# SM3320-BATT-EV.net
KiCad netlist of a schematic drawn in Altium Designer
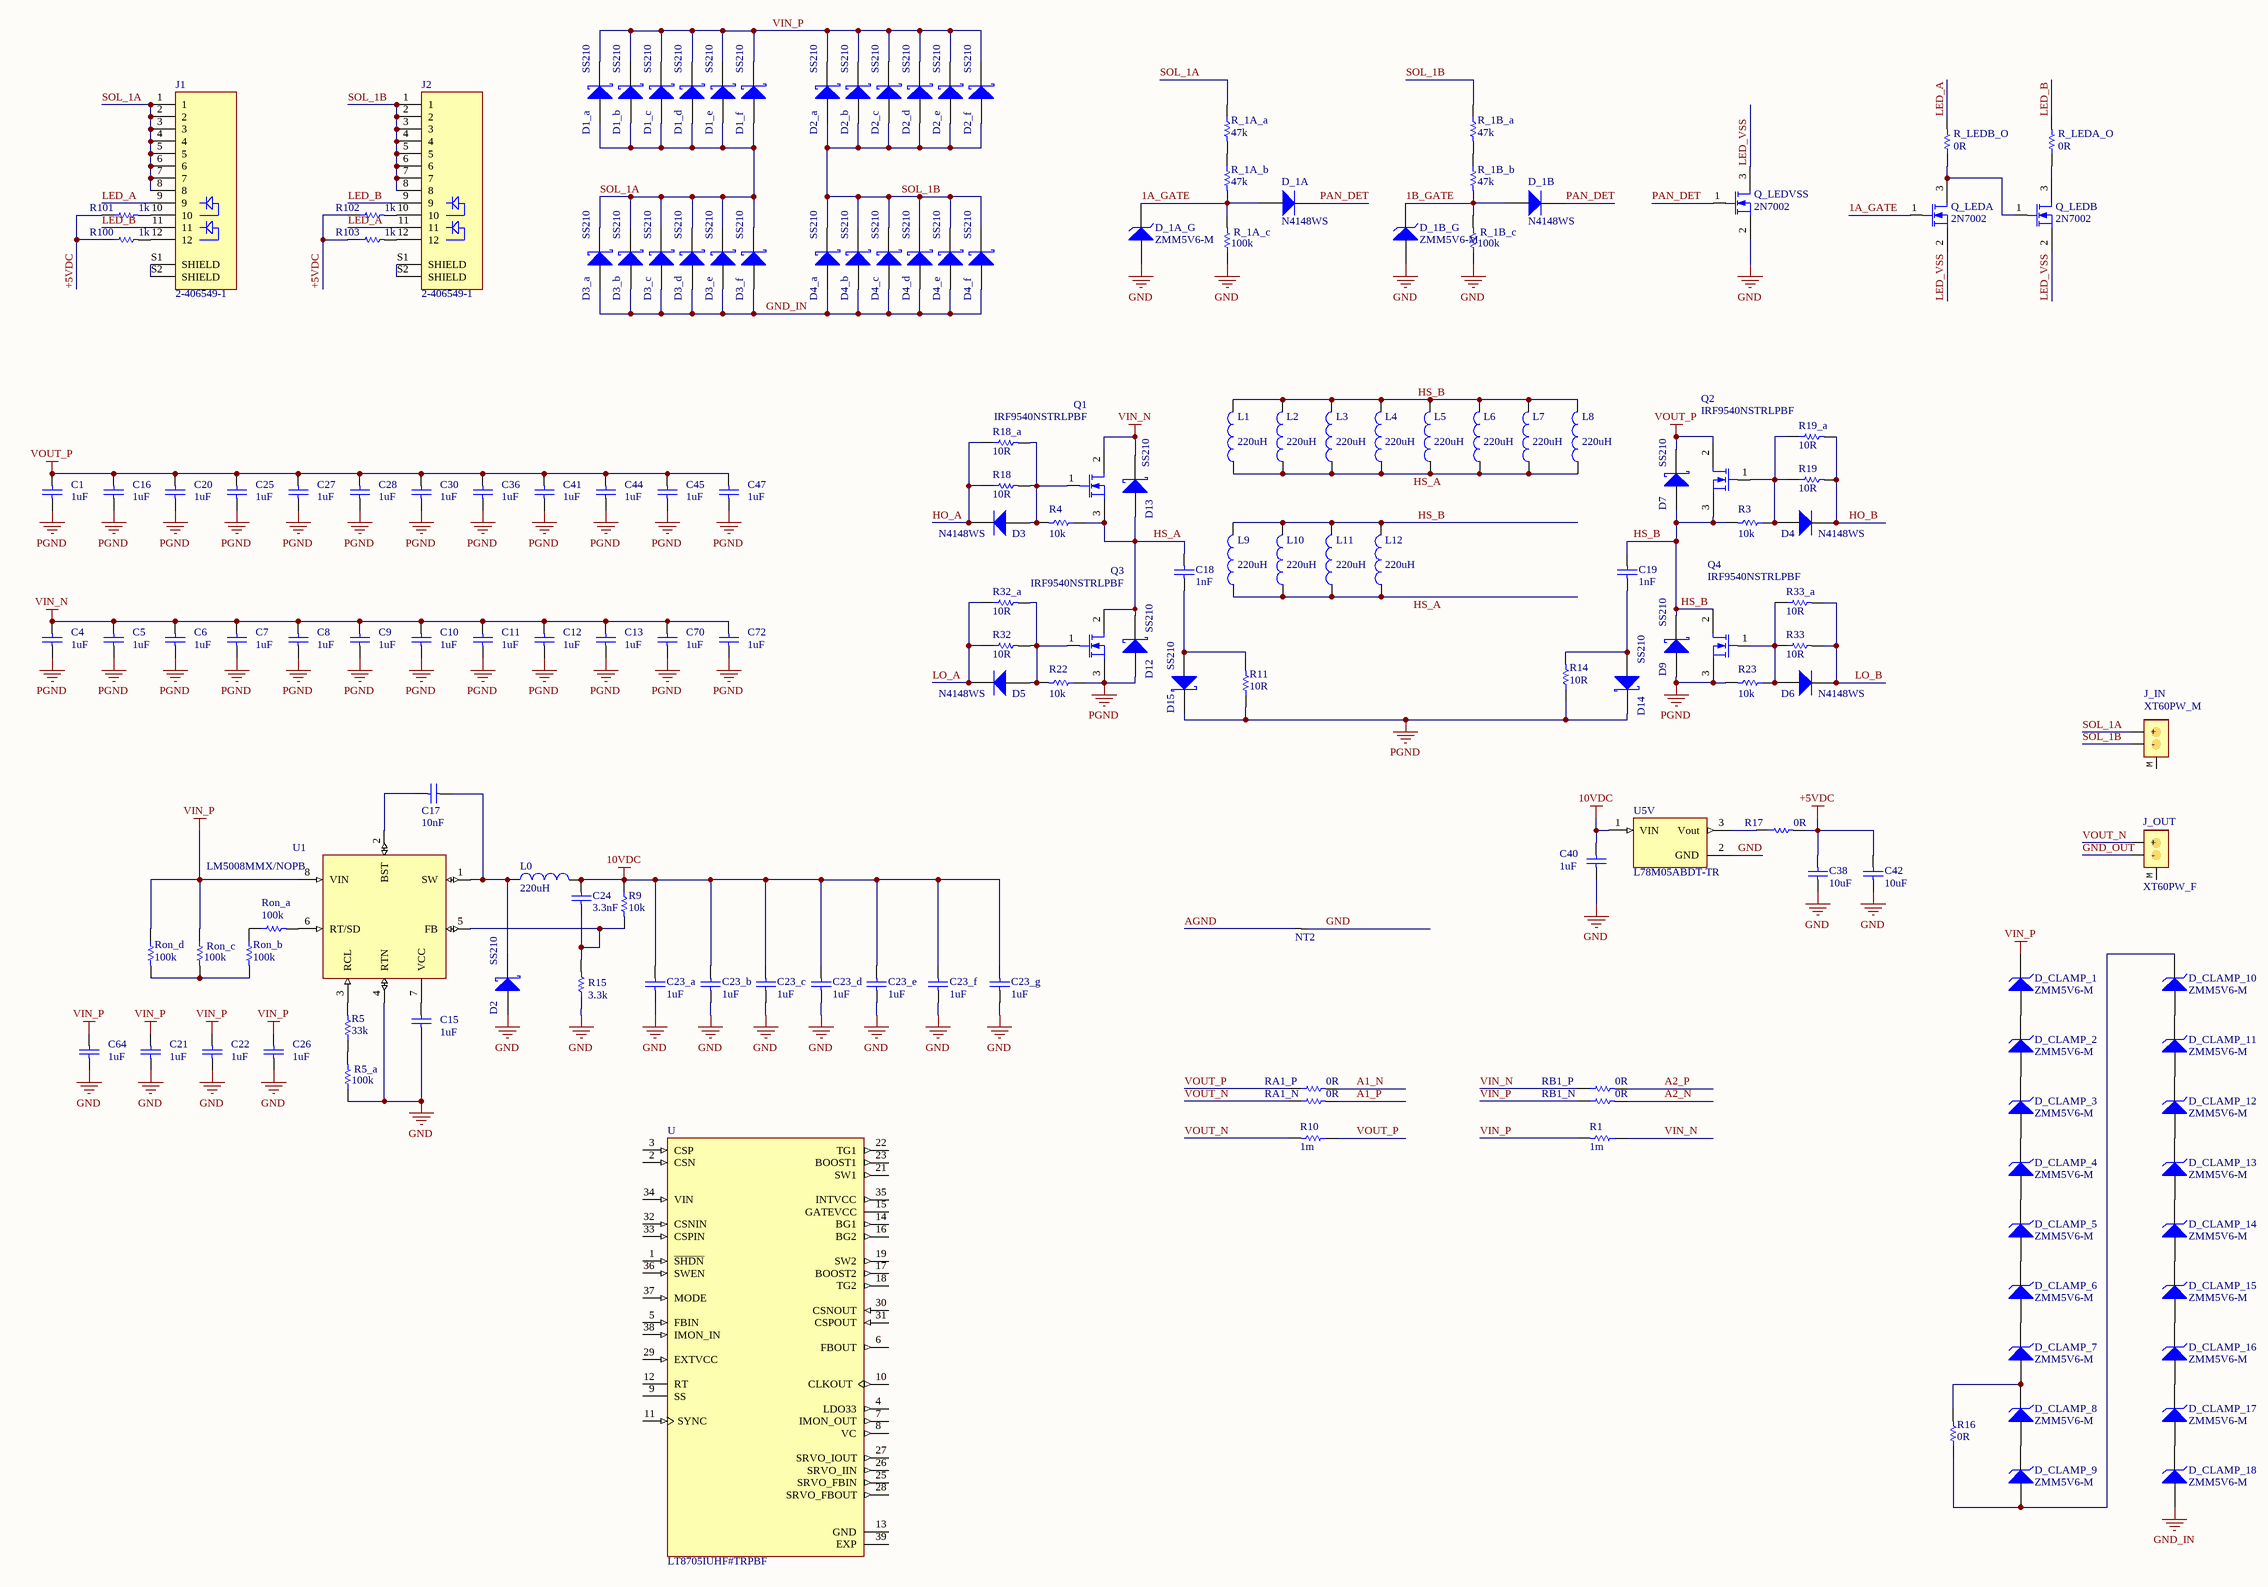
[diagram p0: SM3320-BATT-EV.SchDoc]

(export (version "E")
  (design (tool "Eeschema 10.0.6"))
  (components
    (comp (ref "C1")
      (value "1uF")
      (footprint "C_1206")
      (description "C - CAPACITOR - MLCC - 1uF - 100V - 1206 - X7R")
      (fields (field (name "LCSC PART #") "C91151") (field (name "Comment") "1206B105K101NT"))
      (libsource (lib "JLC_PCB") (part "1206B105K101NT"))
    )
    (comp (ref "C4")
      (value "1uF")
      (footprint "C_1206")
      (description "C - CAPACITOR - MLCC - 1uF - 100V - 1206 - X7R")
      (fields (field (name "LCSC PART #") "C91151") (field (name "Comment") "1206B105K101NT"))
      (libsource (lib "JLC_PCB") (part "1206B105K101NT"))
    )
    (comp (ref "C5")
      (value "1uF")
      (footprint "C_1206")
      (description "C - CAPACITOR - MLCC - 1uF - 100V - 1206 - X7R")
      (fields (field (name "LCSC PART #") "C91151") (field (name "Comment") "1206B105K101NT"))
      (libsource (lib "JLC_PCB") (part "1206B105K101NT"))
    )
    (comp (ref "C6")
      (value "1uF")
      (footprint "C_1206")
      (description "C - CAPACITOR - MLCC - 1uF - 100V - 1206 - X7R")
      (fields (field (name "LCSC PART #") "C91151") (field (name "Comment") "1206B105K101NT"))
      (libsource (lib "JLC_PCB") (part "1206B105K101NT"))
    )
    (comp (ref "C7")
      (value "1uF")
      (footprint "C_1206")
      (description "C - CAPACITOR - MLCC - 1uF - 100V - 1206 - X7R")
      (fields (field (name "LCSC PART #") "C91151") (field (name "Comment") "1206B105K101NT"))
      (libsource (lib "JLC_PCB") (part "1206B105K101NT"))
    )
    (comp (ref "C8")
      (value "1uF")
      (footprint "C_1206")
      (description "C - CAPACITOR - MLCC - 1uF - 100V - 1206 - X7R")
      (fields (field (name "LCSC PART #") "C91151") (field (name "Comment") "1206B105K101NT"))
      (libsource (lib "JLC_PCB") (part "1206B105K101NT"))
    )
    (comp (ref "C9")
      (value "1uF")
      (footprint "C_1206")
      (description "C - CAPACITOR - MLCC - 1uF - 100V - 1206 - X7R")
      (fields (field (name "LCSC PART #") "C91151") (field (name "Comment") "1206B105K101NT"))
      (libsource (lib "JLC_PCB") (part "1206B105K101NT"))
    )
    (comp (ref "C10")
      (value "1uF")
      (footprint "C_1206")
      (description "C - CAPACITOR - MLCC - 1uF - 100V - 1206 - X7R")
      (fields (field (name "LCSC PART #") "C91151") (field (name "Comment") "1206B105K101NT"))
      (libsource (lib "JLC_PCB") (part "1206B105K101NT"))
    )
    (comp (ref "C11")
      (value "1uF")
      (footprint "C_1206")
      (description "C - CAPACITOR - MLCC - 1uF - 100V - 1206 - X7R")
      (fields (field (name "LCSC PART #") "C91151") (field (name "Comment") "1206B105K101NT"))
      (libsource (lib "JLC_PCB") (part "1206B105K101NT"))
    )
    (comp (ref "C12")
      (value "1uF")
      (footprint "C_1206")
      (description "C - CAPACITOR - MLCC - 1uF - 100V - 1206 - X7R")
      (fields (field (name "LCSC PART #") "C91151") (field (name "Comment") "1206B105K101NT"))
      (libsource (lib "JLC_PCB") (part "1206B105K101NT"))
    )
    (comp (ref "C13")
      (value "1uF")
      (footprint "C_1206")
      (description "C - CAPACITOR - MLCC - 1uF - 100V - 1206 - X7R")
      (fields (field (name "LCSC PART #") "C91151") (field (name "Comment") "1206B105K101NT"))
      (libsource (lib "JLC_PCB") (part "1206B105K101NT"))
    )
    (comp (ref "C15")
      (value "1uF")
      (footprint "C_0402")
      (description "C - CAPACITOR - MLCC - 1uF - 25V - 0402")
      (fields (field (name "LCSC PART #") "C52923") (field (name "Comment") "CL05A105KA5NQNC"))
      (libsource (lib "JLC_PCB") (part "CL05A105KA5NQNC"))
    )
    (comp (ref "C16")
      (value "1uF")
      (footprint "C_1206")
      (description "C - CAPACITOR - MLCC - 1uF - 100V - 1206 - X7R")
      (fields (field (name "LCSC PART #") "C91151") (field (name "Comment") "1206B105K101NT"))
      (libsource (lib "JLC_PCB") (part "1206B105K101NT"))
    )
    (comp (ref "C17")
      (value "10nF")
      (footprint "C_0402")
      (description "C - CAPACITOR - MLCC - 10nF - 50V - 0402")
      (fields (field (name "LCSC PART #") "C15195") (field (name "Comment") "CL05B103KB5NNNC"))
      (libsource (lib "JLC_PCB") (part "CL05B103KB5NNNC"))
    )
    (comp (ref "C18")
      (value "1nF")
      (footprint "C_1206")
      (description "C - CAPACITOR - MLCC - 1nF - 2000V - 1206 - X7R")
      (fields (field (name "LCSC PART #") "C9196") (field (name "Comment") "1206B102K202NT"))
      (libsource (lib "JLC_PCB") (part "1206B102K202NT"))
    )
    (comp (ref "C19")
      (value "1nF")
      (footprint "C_1206")
      (description "C - CAPACITOR - MLCC - 1nF - 2000V - 1206 - X7R")
      (fields (field (name "LCSC PART #") "C9196") (field (name "Comment") "1206B102K202NT"))
      (libsource (lib "JLC_PCB") (part "1206B102K202NT"))
    )
    (comp (ref "C20")
      (value "1uF")
      (footprint "C_1206")
      (description "C - CAPACITOR - MLCC - 1uF - 100V - 1206 - X7R")
      (fields (field (name "LCSC PART #") "C91151") (field (name "Comment") "1206B105K101NT"))
      (libsource (lib "JLC_PCB") (part "1206B105K101NT"))
    )
    (comp (ref "C21")
      (value "1uF")
      (footprint "C_1206")
      (description "C - CAPACITOR - MLCC - 1uF - 100V - 1206 - X7R")
      (fields (field (name "LCSC PART #") "C91151") (field (name "Comment") "1206B105K101NT"))
      (libsource (lib "JLC_PCB") (part "1206B105K101NT"))
    )
    (comp (ref "C22")
      (value "1uF")
      (footprint "C_1206")
      (description "C - CAPACITOR - MLCC - 1uF - 100V - 1206 - X7R")
      (fields (field (name "LCSC PART #") "C91151") (field (name "Comment") "1206B105K101NT"))
      (libsource (lib "JLC_PCB") (part "1206B105K101NT"))
    )
    (comp (ref "C23_a")
      (value "1uF")
      (footprint "C_0402")
      (description "C - CAPACITOR - MLCC - 1uF - 25V - 0402")
      (fields (field (name "LCSC PART #") "C52923") (field (name "Comment") "CL05A105KA5NQNC"))
      (libsource (lib "JLC_PCB") (part "CL05A105KA5NQNC"))
    )
    (comp (ref "C23_b")
      (value "1uF")
      (footprint "C_0402")
      (description "C - CAPACITOR - MLCC - 1uF - 25V - 0402")
      (fields (field (name "LCSC PART #") "C52923") (field (name "Comment") "CL05A105KA5NQNC"))
      (libsource (lib "JLC_PCB") (part "CL05A105KA5NQNC"))
    )
    (comp (ref "C23_c")
      (value "1uF")
      (footprint "C_0402")
      (description "C - CAPACITOR - MLCC - 1uF - 25V - 0402")
      (fields (field (name "LCSC PART #") "C52923") (field (name "Comment") "CL05A105KA5NQNC"))
      (libsource (lib "JLC_PCB") (part "CL05A105KA5NQNC"))
    )
    (comp (ref "C23_d")
      (value "1uF")
      (footprint "C_0402")
      (description "C - CAPACITOR - MLCC - 1uF - 25V - 0402")
      (fields (field (name "LCSC PART #") "C52923") (field (name "Comment") "CL05A105KA5NQNC"))
      (libsource (lib "JLC_PCB") (part "CL05A105KA5NQNC"))
    )
    (comp (ref "C23_e")
      (value "1uF")
      (footprint "C_0402")
      (description "C - CAPACITOR - MLCC - 1uF - 25V - 0402")
      (fields (field (name "LCSC PART #") "C52923") (field (name "Comment") "CL05A105KA5NQNC"))
      (libsource (lib "JLC_PCB") (part "CL05A105KA5NQNC"))
    )
    (comp (ref "C23_f")
      (value "1uF")
      (footprint "C_0402")
      (description "C - CAPACITOR - MLCC - 1uF - 25V - 0402")
      (fields (field (name "LCSC PART #") "C52923") (field (name "Comment") "CL05A105KA5NQNC"))
      (libsource (lib "JLC_PCB") (part "CL05A105KA5NQNC"))
    )
    (comp (ref "C23_g")
      (value "1uF")
      (footprint "C_0402")
      (description "C - CAPACITOR - MLCC - 1uF - 25V - 0402")
      (fields (field (name "LCSC PART #") "C52923") (field (name "Comment") "CL05A105KA5NQNC"))
      (libsource (lib "JLC_PCB") (part "CL05A105KA5NQNC"))
    )
    (comp (ref "C24")
      (value "3.3nF")
      (footprint "C_0402")
      (description "C - CAPACITOR - MLCC - 3.3nF - 50V - 0402")
      (fields (field (name "LCSC PART #") "C26404") (field (name "Comment") "CL05B332KB5NNNC"))
      (libsource (lib "JLC_PCB") (part "CL05B332KB5NNNC"))
    )
    (comp (ref "C25")
      (value "1uF")
      (footprint "C_1206")
      (description "C - CAPACITOR - MLCC - 1uF - 100V - 1206 - X7R")
      (fields (field (name "LCSC PART #") "C91151") (field (name "Comment") "1206B105K101NT"))
      (libsource (lib "JLC_PCB") (part "1206B105K101NT"))
    )
    (comp (ref "C26")
      (value "1uF")
      (footprint "C_1206")
      (description "C - CAPACITOR - MLCC - 1uF - 100V - 1206 - X7R")
      (fields (field (name "LCSC PART #") "C91151") (field (name "Comment") "1206B105K101NT"))
      (libsource (lib "JLC_PCB") (part "1206B105K101NT"))
    )
    (comp (ref "C27")
      (value "1uF")
      (footprint "C_1206")
      (description "C - CAPACITOR - MLCC - 1uF - 100V - 1206 - X7R")
      (fields (field (name "LCSC PART #") "C91151") (field (name "Comment") "1206B105K101NT"))
      (libsource (lib "JLC_PCB") (part "1206B105K101NT"))
    )
    (comp (ref "C28")
      (value "1uF")
      (footprint "C_1206")
      (description "C - CAPACITOR - MLCC - 1uF - 100V - 1206 - X7R")
      (fields (field (name "LCSC PART #") "C91151") (field (name "Comment") "1206B105K101NT"))
      (libsource (lib "JLC_PCB") (part "1206B105K101NT"))
    )
    (comp (ref "C30")
      (value "1uF")
      (footprint "C_1206")
      (description "C - CAPACITOR - MLCC - 1uF - 100V - 1206 - X7R")
      (fields (field (name "LCSC PART #") "C91151") (field (name "Comment") "1206B105K101NT"))
      (libsource (lib "JLC_PCB") (part "1206B105K101NT"))
    )
    (comp (ref "C36")
      (value "1uF")
      (footprint "C_1206")
      (description "C - CAPACITOR - MLCC - 1uF - 100V - 1206 - X7R")
      (fields (field (name "LCSC PART #") "C91151") (field (name "Comment") "1206B105K101NT"))
      (libsource (lib "JLC_PCB") (part "1206B105K101NT"))
    )
    (comp (ref "C38")
      (value "10uF")
      (footprint "C_0402")
      (description "C - CAPACITOR - MLCC - 10uF - 6.3V - 0402")
      (fields (field (name "LCSC PART #") "C15525") (field (name "Comment") "CL05A106MQ5NUNC"))
      (libsource (lib "JLC_PCB") (part "CL05A106MQ5NUNC"))
    )
    (comp (ref "C40")
      (value "1uF")
      (footprint "C_0402")
      (description "C - CAPACITOR - MLCC - 1uF - 25V - 0402")
      (fields (field (name "LCSC PART #") "C52923") (field (name "Comment") "CL05A105KA5NQNC"))
      (libsource (lib "JLC_PCB") (part "CL05A105KA5NQNC"))
    )
    (comp (ref "C41")
      (value "1uF")
      (footprint "C_1206")
      (description "C - CAPACITOR - MLCC - 1uF - 100V - 1206 - X7R")
      (fields (field (name "LCSC PART #") "C91151") (field (name "Comment") "1206B105K101NT"))
      (libsource (lib "JLC_PCB") (part "1206B105K101NT"))
    )
    (comp (ref "C42")
      (value "10uF")
      (footprint "C_0402")
      (description "C - CAPACITOR - MLCC - 10uF - 6.3V - 0402")
      (fields (field (name "LCSC PART #") "C15525") (field (name "Comment") "CL05A106MQ5NUNC"))
      (libsource (lib "JLC_PCB") (part "CL05A106MQ5NUNC"))
    )
    (comp (ref "C44")
      (value "1uF")
      (footprint "C_1206")
      (description "C - CAPACITOR - MLCC - 1uF - 100V - 1206 - X7R")
      (fields (field (name "LCSC PART #") "C91151") (field (name "Comment") "1206B105K101NT"))
      (libsource (lib "JLC_PCB") (part "1206B105K101NT"))
    )
    (comp (ref "C45")
      (value "1uF")
      (footprint "C_1206")
      (description "C - CAPACITOR - MLCC - 1uF - 100V - 1206 - X7R")
      (fields (field (name "LCSC PART #") "C91151") (field (name "Comment") "1206B105K101NT"))
      (libsource (lib "JLC_PCB") (part "1206B105K101NT"))
    )
    (comp (ref "C47")
      (value "1uF")
      (footprint "C_1206")
      (description "C - CAPACITOR - MLCC - 1uF - 100V - 1206 - X7R")
      (fields (field (name "LCSC PART #") "C91151") (field (name "Comment") "1206B105K101NT"))
      (libsource (lib "JLC_PCB") (part "1206B105K101NT"))
    )
    (comp (ref "C64")
      (value "1uF")
      (footprint "C_1206")
      (description "C - CAPACITOR - MLCC - 1uF - 100V - 1206 - X7R")
      (fields (field (name "LCSC PART #") "C91151") (field (name "Comment") "1206B105K101NT"))
      (libsource (lib "JLC_PCB") (part "1206B105K101NT"))
    )
    (comp (ref "C70")
      (value "1uF")
      (footprint "C_1206")
      (description "C - CAPACITOR - MLCC - 1uF - 100V - 1206 - X7R")
      (fields (field (name "LCSC PART #") "C91151") (field (name "Comment") "1206B105K101NT"))
      (libsource (lib "JLC_PCB") (part "1206B105K101NT"))
    )
    (comp (ref "C72")
      (value "1uF")
      (footprint "C_1206")
      (description "C - CAPACITOR - MLCC - 1uF - 100V - 1206 - X7R")
      (fields (field (name "LCSC PART #") "C91151") (field (name "Comment") "1206B105K101NT"))
      (libsource (lib "JLC_PCB") (part "1206B105K101NT"))
    )
    (comp (ref "D1_a")
      (value "SS210")
      (footprint "DO-214AC")
      (description "D - DIODE - SCHOTTKY - 100V - 2A")
      (fields (field (name "LCSC PART #") "C14996"))
      (libsource (lib "JLC_PCB") (part "SS210"))
    )
    (comp (ref "D1_b")
      (value "SS210")
      (footprint "DO-214AC")
      (description "D - DIODE - SCHOTTKY - 100V - 2A")
      (fields (field (name "LCSC PART #") "C14996"))
      (libsource (lib "JLC_PCB") (part "SS210"))
    )
    (comp (ref "D1_c")
      (value "SS210")
      (footprint "DO-214AC")
      (description "D - DIODE - SCHOTTKY - 100V - 2A")
      (fields (field (name "LCSC PART #") "C14996"))
      (libsource (lib "JLC_PCB") (part "SS210"))
    )
    (comp (ref "D1_d")
      (value "SS210")
      (footprint "DO-214AC")
      (description "D - DIODE - SCHOTTKY - 100V - 2A")
      (fields (field (name "LCSC PART #") "C14996"))
      (libsource (lib "JLC_PCB") (part "SS210"))
    )
    (comp (ref "D1_e")
      (value "SS210")
      (footprint "DO-214AC")
      (description "D - DIODE - SCHOTTKY - 100V - 2A")
      (fields (field (name "LCSC PART #") "C14996"))
      (libsource (lib "JLC_PCB") (part "SS210"))
    )
    (comp (ref "D1_f")
      (value "SS210")
      (footprint "DO-214AC")
      (description "D - DIODE - SCHOTTKY - 100V - 2A")
      (fields (field (name "LCSC PART #") "C14996"))
      (libsource (lib "JLC_PCB") (part "SS210"))
    )
    (comp (ref "D2")
      (value "SS210")
      (footprint "DO-214AC")
      (description "D - DIODE - SCHOTTKY - 100V - 2A")
      (fields (field (name "LCSC PART #") "C14996"))
      (libsource (lib "JLC_PCB") (part "SS210"))
    )
    (comp (ref "D2_a")
      (value "SS210")
      (footprint "DO-214AC")
      (description "D - DIODE - SCHOTTKY - 100V - 2A")
      (fields (field (name "LCSC PART #") "C14996"))
      (libsource (lib "JLC_PCB") (part "SS210"))
    )
    (comp (ref "D2_b")
      (value "SS210")
      (footprint "DO-214AC")
      (description "D - DIODE - SCHOTTKY - 100V - 2A")
      (fields (field (name "LCSC PART #") "C14996"))
      (libsource (lib "JLC_PCB") (part "SS210"))
    )
    (comp (ref "D2_c")
      (value "SS210")
      (footprint "DO-214AC")
      (description "D - DIODE - SCHOTTKY - 100V - 2A")
      (fields (field (name "LCSC PART #") "C14996"))
      (libsource (lib "JLC_PCB") (part "SS210"))
    )
    (comp (ref "D2_d")
      (value "SS210")
      (footprint "DO-214AC")
      (description "D - DIODE - SCHOTTKY - 100V - 2A")
      (fields (field (name "LCSC PART #") "C14996"))
      (libsource (lib "JLC_PCB") (part "SS210"))
    )
    (comp (ref "D2_e")
      (value "SS210")
      (footprint "DO-214AC")
      (description "D - DIODE - SCHOTTKY - 100V - 2A")
      (fields (field (name "LCSC PART #") "C14996"))
      (libsource (lib "JLC_PCB") (part "SS210"))
    )
    (comp (ref "D2_f")
      (value "SS210")
      (footprint "DO-214AC")
      (description "D - DIODE - SCHOTTKY - 100V - 2A")
      (fields (field (name "LCSC PART #") "C14996"))
      (libsource (lib "JLC_PCB") (part "SS210"))
    )
    (comp (ref "D3")
      (value "N4148WS")
      (footprint "SOD-323")
      (description "D - DIODE - FAST TRR - 100V - 150mA - 4ns")
      (fields (field (name "LCSC PART #") "C2128"))
      (libsource (lib "JLC_PCB") (part "N4148WS"))
    )
    (comp (ref "D3_a")
      (value "SS210")
      (footprint "DO-214AC")
      (description "D - DIODE - SCHOTTKY - 100V - 2A")
      (fields (field (name "LCSC PART #") "C14996"))
      (libsource (lib "JLC_PCB") (part "SS210"))
    )
    (comp (ref "D3_b")
      (value "SS210")
      (footprint "DO-214AC")
      (description "D - DIODE - SCHOTTKY - 100V - 2A")
      (fields (field (name "LCSC PART #") "C14996"))
      (libsource (lib "JLC_PCB") (part "SS210"))
    )
    (comp (ref "D3_c")
      (value "SS210")
      (footprint "DO-214AC")
      (description "D - DIODE - SCHOTTKY - 100V - 2A")
      (fields (field (name "LCSC PART #") "C14996"))
      (libsource (lib "JLC_PCB") (part "SS210"))
    )
    (comp (ref "D3_d")
      (value "SS210")
      (footprint "DO-214AC")
      (description "D - DIODE - SCHOTTKY - 100V - 2A")
      (fields (field (name "LCSC PART #") "C14996"))
      (libsource (lib "JLC_PCB") (part "SS210"))
    )
    (comp (ref "D3_e")
      (value "SS210")
      (footprint "DO-214AC")
      (description "D - DIODE - SCHOTTKY - 100V - 2A")
      (fields (field (name "LCSC PART #") "C14996"))
      (libsource (lib "JLC_PCB") (part "SS210"))
    )
    (comp (ref "D3_f")
      (value "SS210")
      (footprint "DO-214AC")
      (description "D - DIODE - SCHOTTKY - 100V - 2A")
      (fields (field (name "LCSC PART #") "C14996"))
      (libsource (lib "JLC_PCB") (part "SS210"))
    )
    (comp (ref "D4")
      (value "N4148WS")
      (footprint "SOD-323")
      (description "D - DIODE - FAST TRR - 100V - 150mA - 4ns")
      (fields (field (name "LCSC PART #") "C2128"))
      (libsource (lib "JLC_PCB") (part "N4148WS"))
    )
    (comp (ref "D4_a")
      (value "SS210")
      (footprint "DO-214AC")
      (description "D - DIODE - SCHOTTKY - 100V - 2A")
      (fields (field (name "LCSC PART #") "C14996"))
      (libsource (lib "JLC_PCB") (part "SS210"))
    )
    (comp (ref "D4_b")
      (value "SS210")
      (footprint "DO-214AC")
      (description "D - DIODE - SCHOTTKY - 100V - 2A")
      (fields (field (name "LCSC PART #") "C14996"))
      (libsource (lib "JLC_PCB") (part "SS210"))
    )
    (comp (ref "D4_c")
      (value "SS210")
      (footprint "DO-214AC")
      (description "D - DIODE - SCHOTTKY - 100V - 2A")
      (fields (field (name "LCSC PART #") "C14996"))
      (libsource (lib "JLC_PCB") (part "SS210"))
    )
    (comp (ref "D4_d")
      (value "SS210")
      (footprint "DO-214AC")
      (description "D - DIODE - SCHOTTKY - 100V - 2A")
      (fields (field (name "LCSC PART #") "C14996"))
      (libsource (lib "JLC_PCB") (part "SS210"))
    )
    (comp (ref "D4_e")
      (value "SS210")
      (footprint "DO-214AC")
      (description "D - DIODE - SCHOTTKY - 100V - 2A")
      (fields (field (name "LCSC PART #") "C14996"))
      (libsource (lib "JLC_PCB") (part "SS210"))
    )
    (comp (ref "D4_f")
      (value "SS210")
      (footprint "DO-214AC")
      (description "D - DIODE - SCHOTTKY - 100V - 2A")
      (fields (field (name "LCSC PART #") "C14996"))
      (libsource (lib "JLC_PCB") (part "SS210"))
    )
    (comp (ref "D5")
      (value "N4148WS")
      (footprint "SOD-323")
      (description "D - DIODE - FAST TRR - 100V - 150mA - 4ns")
      (fields (field (name "LCSC PART #") "C2128"))
      (libsource (lib "JLC_PCB") (part "N4148WS"))
    )
    (comp (ref "D6")
      (value "N4148WS")
      (footprint "SOD-323")
      (description "D - DIODE - FAST TRR - 100V - 150mA - 4ns")
      (fields (field (name "LCSC PART #") "C2128"))
      (libsource (lib "JLC_PCB") (part "N4148WS"))
    )
    (comp (ref "D7")
      (value "SS210")
      (footprint "DO-214AC")
      (description "D - DIODE - SCHOTTKY - 100V - 2A")
      (fields (field (name "LCSC PART #") "C14996"))
      (libsource (lib "JLC_PCB") (part "SS210"))
    )
    (comp (ref "D9")
      (value "SS210")
      (footprint "DO-214AC")
      (description "D - DIODE - SCHOTTKY - 100V - 2A")
      (fields (field (name "LCSC PART #") "C14996"))
      (libsource (lib "JLC_PCB") (part "SS210"))
    )
    (comp (ref "D12")
      (value "SS210")
      (footprint "DO-214AC")
      (description "D - DIODE - SCHOTTKY - 100V - 2A")
      (fields (field (name "LCSC PART #") "C14996"))
      (libsource (lib "JLC_PCB") (part "SS210"))
    )
    (comp (ref "D13")
      (value "SS210")
      (footprint "DO-214AC")
      (description "D - DIODE - SCHOTTKY - 100V - 2A")
      (fields (field (name "LCSC PART #") "C14996"))
      (libsource (lib "JLC_PCB") (part "SS210"))
    )
    (comp (ref "D14")
      (value "SS210")
      (footprint "DO-214AC")
      (description "D - DIODE - SCHOTTKY - 100V - 2A")
      (fields (field (name "LCSC PART #") "C14996"))
      (libsource (lib "JLC_PCB") (part "SS210"))
    )
    (comp (ref "D15")
      (value "SS210")
      (footprint "DO-214AC")
      (description "D - DIODE - SCHOTTKY - 100V - 2A")
      (fields (field (name "LCSC PART #") "C14996"))
      (libsource (lib "JLC_PCB") (part "SS210"))
    )
    (comp (ref "D_1A")
      (value "N4148WS")
      (footprint "SOD-323")
      (description "D - DIODE - FAST TRR - 100V - 150mA - 4ns")
      (fields (field (name "LCSC PART #") "C2128"))
      (libsource (lib "JLC_PCB") (part "N4148WS"))
    )
    (comp (ref "D_1A_G")
      (value "ZMM5V6-M")
      (footprint "DO-213AA")
      (description "D - DIODE - ZENER - 5.6V - 500mW")
      (fields (field (name "LCSC PART #") "C8062"))
      (libsource (lib "JLC_PCB") (part "ZMM5V6-M"))
    )
    (comp (ref "D_1B")
      (value "N4148WS")
      (footprint "SOD-323")
      (description "D - DIODE - FAST TRR - 100V - 150mA - 4ns")
      (fields (field (name "LCSC PART #") "C2128"))
      (libsource (lib "JLC_PCB") (part "N4148WS"))
    )
    (comp (ref "D_1B_G")
      (value "ZMM5V6-M")
      (footprint "DO-213AA")
      (description "D - DIODE - ZENER - 5.6V - 500mW")
      (fields (field (name "LCSC PART #") "C8062"))
      (libsource (lib "JLC_PCB") (part "ZMM5V6-M"))
    )
    (comp (ref "D_CLAMP_1")
      (value "ZMM5V6-M")
      (footprint "DO-213AA")
      (description "D - DIODE - ZENER - 5.6V - 500mW")
      (fields (field (name "LCSC PART #") "C8062"))
      (libsource (lib "JLC_PCB") (part "ZMM5V6-M"))
    )
    (comp (ref "D_CLAMP_2")
      (value "ZMM5V6-M")
      (footprint "DO-213AA")
      (description "D - DIODE - ZENER - 5.6V - 500mW")
      (fields (field (name "LCSC PART #") "C8062"))
      (libsource (lib "JLC_PCB") (part "ZMM5V6-M"))
    )
    (comp (ref "D_CLAMP_3")
      (value "ZMM5V6-M")
      (footprint "DO-213AA")
      (description "D - DIODE - ZENER - 5.6V - 500mW")
      (fields (field (name "LCSC PART #") "C8062"))
      (libsource (lib "JLC_PCB") (part "ZMM5V6-M"))
    )
    (comp (ref "D_CLAMP_4")
      (value "ZMM5V6-M")
      (footprint "DO-213AA")
      (description "D - DIODE - ZENER - 5.6V - 500mW")
      (fields (field (name "LCSC PART #") "C8062"))
      (libsource (lib "JLC_PCB") (part "ZMM5V6-M"))
    )
    (comp (ref "D_CLAMP_5")
      (value "ZMM5V6-M")
      (footprint "DO-213AA")
      (description "D - DIODE - ZENER - 5.6V - 500mW")
      (fields (field (name "LCSC PART #") "C8062"))
      (libsource (lib "JLC_PCB") (part "ZMM5V6-M"))
    )
    (comp (ref "D_CLAMP_6")
      (value "ZMM5V6-M")
      (footprint "DO-213AA")
      (description "D - DIODE - ZENER - 5.6V - 500mW")
      (fields (field (name "LCSC PART #") "C8062"))
      (libsource (lib "JLC_PCB") (part "ZMM5V6-M"))
    )
    (comp (ref "D_CLAMP_7")
      (value "ZMM5V6-M")
      (footprint "DO-213AA")
      (description "D - DIODE - ZENER - 5.6V - 500mW")
      (fields (field (name "LCSC PART #") "C8062"))
      (libsource (lib "JLC_PCB") (part "ZMM5V6-M"))
    )
    (comp (ref "D_CLAMP_8")
      (value "ZMM5V6-M")
      (footprint "DO-213AA")
      (description "D - DIODE - ZENER - 5.6V - 500mW")
      (fields (field (name "LCSC PART #") "C8062"))
      (libsource (lib "JLC_PCB") (part "ZMM5V6-M"))
    )
    (comp (ref "D_CLAMP_9")
      (value "ZMM5V6-M")
      (footprint "DO-213AA")
      (description "D - DIODE - ZENER - 5.6V - 500mW")
      (fields (field (name "LCSC PART #") "C8062"))
      (libsource (lib "JLC_PCB") (part "ZMM5V6-M"))
    )
    (comp (ref "D_CLAMP_10")
      (value "ZMM5V6-M")
      (footprint "DO-213AA")
      (description "D - DIODE - ZENER - 5.6V - 500mW")
      (fields (field (name "LCSC PART #") "C8062"))
      (libsource (lib "JLC_PCB") (part "ZMM5V6-M"))
    )
    (comp (ref "D_CLAMP_11")
      (value "ZMM5V6-M")
      (footprint "DO-213AA")
      (description "D - DIODE - ZENER - 5.6V - 500mW")
      (fields (field (name "LCSC PART #") "C8062"))
      (libsource (lib "JLC_PCB") (part "ZMM5V6-M"))
    )
    (comp (ref "D_CLAMP_12")
      (value "ZMM5V6-M")
      (footprint "DO-213AA")
      (description "D - DIODE - ZENER - 5.6V - 500mW")
      (fields (field (name "LCSC PART #") "C8062"))
      (libsource (lib "JLC_PCB") (part "ZMM5V6-M"))
    )
    (comp (ref "D_CLAMP_13")
      (value "ZMM5V6-M")
      (footprint "DO-213AA")
      (description "D - DIODE - ZENER - 5.6V - 500mW")
      (fields (field (name "LCSC PART #") "C8062"))
      (libsource (lib "JLC_PCB") (part "ZMM5V6-M"))
    )
    (comp (ref "D_CLAMP_14")
      (value "ZMM5V6-M")
      (footprint "DO-213AA")
      (description "D - DIODE - ZENER - 5.6V - 500mW")
      (fields (field (name "LCSC PART #") "C8062"))
      (libsource (lib "JLC_PCB") (part "ZMM5V6-M"))
    )
    (comp (ref "D_CLAMP_15")
      (value "ZMM5V6-M")
      (footprint "DO-213AA")
      (description "D - DIODE - ZENER - 5.6V - 500mW")
      (fields (field (name "LCSC PART #") "C8062"))
      (libsource (lib "JLC_PCB") (part "ZMM5V6-M"))
    )
    (comp (ref "D_CLAMP_16")
      (value "ZMM5V6-M")
      (footprint "DO-213AA")
      (description "D - DIODE - ZENER - 5.6V - 500mW")
      (fields (field (name "LCSC PART #") "C8062"))
      (libsource (lib "JLC_PCB") (part "ZMM5V6-M"))
    )
    (comp (ref "D_CLAMP_17")
      (value "ZMM5V6-M")
      (footprint "DO-213AA")
      (description "D - DIODE - ZENER - 5.6V - 500mW")
      (fields (field (name "LCSC PART #") "C8062"))
      (libsource (lib "JLC_PCB") (part "ZMM5V6-M"))
    )
    (comp (ref "D_CLAMP_18")
      (value "ZMM5V6-M")
      (footprint "DO-213AA")
      (description "D - DIODE - ZENER - 5.6V - 500mW")
      (fields (field (name "LCSC PART #") "C8062"))
      (libsource (lib "JLC_PCB") (part "ZMM5V6-M"))
    )
    (comp (ref "J1")
      (value "2-406549-1")
      (footprint "TE_2-406549-1")
      (description "J - JACK - ETHERNET - Right - THT")
      (fields (field (name "LCSC PART #") "C125068"))
      (libsource (lib "JLC_PCB") (part "2-406549-1"))
    )
    (comp (ref "J2")
      (value "2-406549-1")
      (footprint "TE_2-406549-1")
      (description "J - JACK - ETHERNET - Right - THT")
      (fields (field (name "LCSC PART #") "C125068"))
      (libsource (lib "JLC_PCB") (part "2-406549-1"))
    )
    (comp (ref "J_IN")
      (value "XT60PW_M")
      (footprint "XT60PW_M")
      (description "J - JACK - POWER - XT60 - RIGHT - MALE")
      (fields (field (name "LCSC PART #") "X"))
      (libsource (lib "JLC_PCB") (part "XT60PW_M"))
    )
    (comp (ref "J_OUT")
      (value "XT60PW_F")
      (footprint "XT60PW_F")
      (description "J - JACK - POWER - XT60 - RIGHT - FEMALE")
      (fields (field (name "LCSC PART #") "X"))
      (libsource (lib "JLC_PCB") (part "XT60PW_F"))
    )
    (comp (ref "L0")
      (value "220uH")
      (footprint "SRR1260")
      (description "L - INDUCTOR - 220uH - 1.6A - 12.5mm")
      (fields (field (name "LCSC PART #") "C169380") (field (name "Comment") "SWRB1207S-221MT"))
      (libsource (lib "JLC_PCB") (part "SWRB1207S-221MT"))
    )
    (comp (ref "L1")
      (value "220uH")
      (footprint "SRR1260")
      (description "L - INDUCTOR - 220uH - 1.6A - 12.5mm")
      (fields (field (name "LCSC PART #") "C169380") (field (name "Comment") "SWRB1207S-221MT"))
      (libsource (lib "JLC_PCB") (part "SWRB1207S-221MT"))
    )
    (comp (ref "L2")
      (value "220uH")
      (footprint "SRR1260")
      (description "L - INDUCTOR - 220uH - 1.6A - 12.5mm")
      (fields (field (name "LCSC PART #") "C169380") (field (name "Comment") "SWRB1207S-221MT"))
      (libsource (lib "JLC_PCB") (part "SWRB1207S-221MT"))
    )
    (comp (ref "L3")
      (value "220uH")
      (footprint "SRR1260")
      (description "L - INDUCTOR - 220uH - 1.6A - 12.5mm")
      (fields (field (name "LCSC PART #") "C169380") (field (name "Comment") "SWRB1207S-221MT"))
      (libsource (lib "JLC_PCB") (part "SWRB1207S-221MT"))
    )
    (comp (ref "L4")
      (value "220uH")
      (footprint "SRR1260")
      (description "L - INDUCTOR - 220uH - 1.6A - 12.5mm")
      (fields (field (name "LCSC PART #") "C169380") (field (name "Comment") "SWRB1207S-221MT"))
      (libsource (lib "JLC_PCB") (part "SWRB1207S-221MT"))
    )
    (comp (ref "L5")
      (value "220uH")
      (footprint "SRR1260")
      (description "L - INDUCTOR - 220uH - 1.6A - 12.5mm")
      (fields (field (name "LCSC PART #") "C169380") (field (name "Comment") "SWRB1207S-221MT"))
      (libsource (lib "JLC_PCB") (part "SWRB1207S-221MT"))
    )
    (comp (ref "L6")
      (value "220uH")
      (footprint "SRR1260")
      (description "L - INDUCTOR - 220uH - 1.6A - 12.5mm")
      (fields (field (name "LCSC PART #") "C169380") (field (name "Comment") "SWRB1207S-221MT"))
      (libsource (lib "JLC_PCB") (part "SWRB1207S-221MT"))
    )
    (comp (ref "L7")
      (value "220uH")
      (footprint "SRR1260")
      (description "L - INDUCTOR - 220uH - 1.6A - 12.5mm")
      (fields (field (name "LCSC PART #") "C169380") (field (name "Comment") "SWRB1207S-221MT"))
      (libsource (lib "JLC_PCB") (part "SWRB1207S-221MT"))
    )
    (comp (ref "L8")
      (value "220uH")
      (footprint "SRR1260")
      (description "L - INDUCTOR - 220uH - 1.6A - 12.5mm")
      (fields (field (name "LCSC PART #") "C169380") (field (name "Comment") "SWRB1207S-221MT"))
      (libsource (lib "JLC_PCB") (part "SWRB1207S-221MT"))
    )
    (comp (ref "L9")
      (value "220uH")
      (footprint "SRR1260")
      (description "L - INDUCTOR - 220uH - 1.6A - 12.5mm")
      (fields (field (name "LCSC PART #") "C169380") (field (name "Comment") "SWRB1207S-221MT"))
      (libsource (lib "JLC_PCB") (part "SWRB1207S-221MT"))
    )
    (comp (ref "L10")
      (value "220uH")
      (footprint "SRR1260")
      (description "L - INDUCTOR - 220uH - 1.6A - 12.5mm")
      (fields (field (name "LCSC PART #") "C169380") (field (name "Comment") "SWRB1207S-221MT"))
      (libsource (lib "JLC_PCB") (part "SWRB1207S-221MT"))
    )
    (comp (ref "L11")
      (value "220uH")
      (footprint "SRR1260")
      (description "L - INDUCTOR - 220uH - 1.6A - 12.5mm")
      (fields (field (name "LCSC PART #") "C169380") (field (name "Comment") "SWRB1207S-221MT"))
      (libsource (lib "JLC_PCB") (part "SWRB1207S-221MT"))
    )
    (comp (ref "L12")
      (value "220uH")
      (footprint "SRR1260")
      (description "L - INDUCTOR - 220uH - 1.6A - 12.5mm")
      (fields (field (name "LCSC PART #") "C169380") (field (name "Comment") "SWRB1207S-221MT"))
      (libsource (lib "JLC_PCB") (part "SWRB1207S-221MT"))
    )
    (comp (ref "NT2")
      (value "0")
      (footprint "NET_TIE")
      (description "R - Net Tie")
      (libsource (lib "JLC_PCB") (part "NET_TIE"))
    )
    (comp (ref "Q1")
      (value "IRF9540NSTRLPBF")
      (footprint "TO-263-3")
      (description "Q - TRANSISTOR - MOSFET (N) - 250V - 33A - 0.094R")
      (fields (field (name "LCSC PART #") "C33903"))
      (libsource (lib "JLC_PCB") (part "IRF9540NSTRLPBF"))
    )
    (comp (ref "Q2")
      (value "IRF9540NSTRLPBF")
      (footprint "TO-263-3")
      (description "Q - TRANSISTOR - MOSFET (N) - 250V - 33A - 0.094R")
      (fields (field (name "LCSC PART #") "C33903"))
      (libsource (lib "JLC_PCB") (part "IRF9540NSTRLPBF"))
    )
    (comp (ref "Q3")
      (value "IRF9540NSTRLPBF")
      (footprint "TO-263-3")
      (description "Q - TRANSISTOR - MOSFET (N) - 250V - 33A - 0.094R")
      (fields (field (name "LCSC PART #") "C33903"))
      (libsource (lib "JLC_PCB") (part "IRF9540NSTRLPBF"))
    )
    (comp (ref "Q4")
      (value "IRF9540NSTRLPBF")
      (footprint "TO-263-3")
      (description "Q - TRANSISTOR - MOSFET (N) - 250V - 33A - 0.094R")
      (fields (field (name "LCSC PART #") "C33903"))
      (libsource (lib "JLC_PCB") (part "IRF9540NSTRLPBF"))
    )
    (comp (ref "Q_LEDA")
      (value "2N7002")
      (footprint "TO-236AB")
      (description "Q - TRANSISTOR - MOSFET (N) - 60V - 200mW")
      (fields (field (name "LCSC PART #") "C8545"))
      (libsource (lib "JLC_PCB") (part "2N7002"))
    )
    (comp (ref "Q_LEDB")
      (value "2N7002")
      (footprint "TO-236AB")
      (description "Q - TRANSISTOR - MOSFET (N) - 60V - 200mW")
      (fields (field (name "LCSC PART #") "C8545"))
      (libsource (lib "JLC_PCB") (part "2N7002"))
    )
    (comp (ref "Q_LEDVSS")
      (value "2N7002")
      (footprint "TO-236AB")
      (description "Q - TRANSISTOR - MOSFET (N) - 60V - 200mW")
      (fields (field (name "LCSC PART #") "C8545"))
      (libsource (lib "JLC_PCB") (part "2N7002"))
    )
    (comp (ref "R1")
      (value "1m")
      (footprint "R_2512")
      (description "R - RESISTOR - SMD - 0.001R - 1% - 2512 - 2W - 50ppm/k")
      (fields (field (name "LCSC PART #") "C349153") (field (name "POWER") "2W"))
      (libsource (lib "JLC_PCB") (part "EWSL2512F1L00S9"))
    )
    (comp (ref "R3")
      (value "10k")
      (footprint "R_0402")
      (description "R - RESISTOR - SMD - 10k - 1% - 0402")
      (fields (field (name "LCSC PART #") "C25744") (field (name "Comment") "0402WGF1002TCE"))
      (libsource (lib "JLC_PCB") (part "0402WGF1002TCE"))
    )
    (comp (ref "R4")
      (value "10k")
      (footprint "R_0402")
      (description "R - RESISTOR - SMD - 10k - 1% - 0402")
      (fields (field (name "LCSC PART #") "C25744") (field (name "Comment") "0402WGF1002TCE"))
      (libsource (lib "JLC_PCB") (part "0402WGF1002TCE"))
    )
    (comp (ref "R5")
      (value "33k")
      (footprint "R_0402")
      (description "R - RESISTOR - SMD - 33k - 1% - 0402")
      (fields (field (name "LCSC PART #") "C25779") (field (name "Comment") "0402WGF3302TCE"))
      (libsource (lib "JLC_PCB") (part "0402WGF3302TCE"))
    )
    (comp (ref "R5_a")
      (value "100k")
      (footprint "R_0402")
      (description "R - RESISTOR - SMD - 100k - 1% -  0402")
      (fields (field (name "LCSC PART #") "C25741") (field (name "Comment") "0402WGF1003TCE"))
      (libsource (lib "JLC_PCB") (part "0402WGF1003TCE"))
    )
    (comp (ref "R9")
      (value "10k")
      (footprint "R_0402")
      (description "R - RESISTOR - SMD - 10k - 1% - 0402")
      (fields (field (name "LCSC PART #") "C25744") (field (name "Comment") "0402WGF1002TCE"))
      (libsource (lib "JLC_PCB") (part "0402WGF1002TCE"))
    )
    (comp (ref "R10")
      (value "1m")
      (footprint "R_2512")
      (description "R - RESISTOR - SMD - 0.001R - 1% - 2512 - 2W - 50ppm/k")
      (fields (field (name "LCSC PART #") "C349153") (field (name "POWER") "2W"))
      (libsource (lib "JLC_PCB") (part "EWSL2512F1L00S9"))
    )
    (comp (ref "R11")
      (value "10R")
      (footprint "R_1206")
      (description "R - RESISTOR - SMD - 10R - 1% - 1206")
      (fields (field (name "LCSC PART #") "C17903") (field (name "Comment") "1206W4F100JT5E"))
      (libsource (lib "JLC_PCB") (part "1206W4F100JT5E"))
    )
    (comp (ref "R14")
      (value "10R")
      (footprint "R_1206")
      (description "R - RESISTOR - SMD - 10R - 1% - 1206")
      (fields (field (name "LCSC PART #") "C17903") (field (name "Comment") "1206W4F100JT5E"))
      (libsource (lib "JLC_PCB") (part "1206W4F100JT5E"))
    )
    (comp (ref "R15")
      (value "3.3k")
      (footprint "R_0402")
      (description "R - RESISTOR - SMD - 3.3k - 1% - 0402")
      (fields (field (name "LCSC PART #") "C25890") (field (name "Comment") "0402WGF3301TCE"))
      (libsource (lib "JLC_PCB") (part "0402WGF3301TCE"))
    )
    (comp (ref "R16")
      (value "0R")
      (footprint "R_0402")
      (description "R - RESISTOR - SMD - 0R - 1% - 0402")
      (fields (field (name "LCSC PART #") "C17168") (field (name "Comment") "0402WGF0000TCE"))
      (libsource (lib "JLC_PCB") (part "0402WGF0000TCE"))
    )
    (comp (ref "R17")
      (value "0R")
      (footprint "R_0402")
      (description "R - RESISTOR - SMD - 0R - 1% - 0402")
      (fields (field (name "LCSC PART #") "C17168") (field (name "Comment") "0402WGF0000TCE"))
      (libsource (lib "JLC_PCB") (part "0402WGF0000TCE"))
    )
    (comp (ref "R18")
      (value "10R")
      (footprint "R_0402")
      (description "R - RESISTOR - SMD - 10R - 1% - 0402")
      (fields (field (name "LCSC PART #") "C25077") (field (name "Comment") "0402WGF100JTCE"))
      (libsource (lib "JLC_PCB") (part "0402WGF100JTCE"))
    )
    (comp (ref "R18_a")
      (value "10R")
      (footprint "R_0402")
      (description "R - RESISTOR - SMD - 10R - 1% - 0402")
      (fields (field (name "LCSC PART #") "C25077") (field (name "Comment") "0402WGF100JTCE"))
      (libsource (lib "JLC_PCB") (part "0402WGF100JTCE"))
    )
    (comp (ref "R19")
      (value "10R")
      (footprint "R_0402")
      (description "R - RESISTOR - SMD - 10R - 1% - 0402")
      (fields (field (name "LCSC PART #") "C25077") (field (name "Comment") "0402WGF100JTCE"))
      (libsource (lib "JLC_PCB") (part "0402WGF100JTCE"))
    )
    (comp (ref "R19_a")
      (value "10R")
      (footprint "R_0402")
      (description "R - RESISTOR - SMD - 10R - 1% - 0402")
      (fields (field (name "LCSC PART #") "C25077") (field (name "Comment") "0402WGF100JTCE"))
      (libsource (lib "JLC_PCB") (part "0402WGF100JTCE"))
    )
    (comp (ref "R22")
      (value "10k")
      (footprint "R_0402")
      (description "R - RESISTOR - SMD - 10k - 1% - 0402")
      (fields (field (name "LCSC PART #") "C25744") (field (name "Comment") "0402WGF1002TCE"))
      (libsource (lib "JLC_PCB") (part "0402WGF1002TCE"))
    )
    (comp (ref "R23")
      (value "10k")
      (footprint "R_0402")
      (description "R - RESISTOR - SMD - 10k - 1% - 0402")
      (fields (field (name "LCSC PART #") "C25744") (field (name "Comment") "0402WGF1002TCE"))
      (libsource (lib "JLC_PCB") (part "0402WGF1002TCE"))
    )
    (comp (ref "R32")
      (value "10R")
      (footprint "R_0402")
      (description "R - RESISTOR - SMD - 10R - 1% - 0402")
      (fields (field (name "LCSC PART #") "C25077") (field (name "Comment") "0402WGF100JTCE"))
      (libsource (lib "JLC_PCB") (part "0402WGF100JTCE"))
    )
    (comp (ref "R32_a")
      (value "10R")
      (footprint "R_0402")
      (description "R - RESISTOR - SMD - 10R - 1% - 0402")
      (fields (field (name "LCSC PART #") "C25077") (field (name "Comment") "0402WGF100JTCE"))
      (libsource (lib "JLC_PCB") (part "0402WGF100JTCE"))
    )
    (comp (ref "R33")
      (value "10R")
      (footprint "R_0402")
      (description "R - RESISTOR - SMD - 10R - 1% - 0402")
      (fields (field (name "LCSC PART #") "C25077") (field (name "Comment") "0402WGF100JTCE"))
      (libsource (lib "JLC_PCB") (part "0402WGF100JTCE"))
    )
    (comp (ref "R33_a")
      (value "10R")
      (footprint "R_0402")
      (description "R - RESISTOR - SMD - 10R - 1% - 0402")
      (fields (field (name "LCSC PART #") "C25077") (field (name "Comment") "0402WGF100JTCE"))
      (libsource (lib "JLC_PCB") (part "0402WGF100JTCE"))
    )
    (comp (ref "R100")
      (value "1k")
      (footprint "R_0402")
      (description "R - RESISTOR - SMD - 1k - 1% - 0402")
      (fields (field (name "LCSC PART #") "C11702") (field (name "Comment") "0402WGF1001TCE"))
      (libsource (lib "JLC_PCB") (part "0402WGF1001TCE"))
    )
    (comp (ref "R101")
      (value "1k")
      (footprint "R_0402")
      (description "R - RESISTOR - SMD - 1k - 1% - 0402")
      (fields (field (name "LCSC PART #") "C11702") (field (name "Comment") "0402WGF1001TCE"))
      (libsource (lib "JLC_PCB") (part "0402WGF1001TCE"))
    )
    (comp (ref "R102")
      (value "1k")
      (footprint "R_0402")
      (description "R - RESISTOR - SMD - 1k - 1% - 0402")
      (fields (field (name "LCSC PART #") "C11702") (field (name "Comment") "0402WGF1001TCE"))
      (libsource (lib "JLC_PCB") (part "0402WGF1001TCE"))
    )
    (comp (ref "R103")
      (value "1k")
      (footprint "R_0402")
      (description "R - RESISTOR - SMD - 1k - 1% - 0402")
      (fields (field (name "LCSC PART #") "C11702") (field (name "Comment") "0402WGF1001TCE"))
      (libsource (lib "JLC_PCB") (part "0402WGF1001TCE"))
    )
    (comp (ref "RA1_N")
      (value "0R")
      (footprint "R_0402")
      (description "R - RESISTOR - SMD - 0R - 1% - 0402")
      (fields (field (name "LCSC PART #") "C17168") (field (name "Comment") "0402WGF0000TCE"))
      (libsource (lib "JLC_PCB") (part "0402WGF0000TCE"))
    )
    (comp (ref "RA1_P")
      (value "0R")
      (footprint "R_0402")
      (description "R - RESISTOR - SMD - 0R - 1% - 0402")
      (fields (field (name "LCSC PART #") "C17168") (field (name "Comment") "0402WGF0000TCE"))
      (libsource (lib "JLC_PCB") (part "0402WGF0000TCE"))
    )
    (comp (ref "RB1_N")
      (value "0R")
      (footprint "R_0402")
      (description "R - RESISTOR - SMD - 0R - 1% - 0402")
      (fields (field (name "LCSC PART #") "C17168") (field (name "Comment") "0402WGF0000TCE"))
      (libsource (lib "JLC_PCB") (part "0402WGF0000TCE"))
    )
    (comp (ref "RB1_P")
      (value "0R")
      (footprint "R_0402")
      (description "R - RESISTOR - SMD - 0R - 1% - 0402")
      (fields (field (name "LCSC PART #") "C17168") (field (name "Comment") "0402WGF0000TCE"))
      (libsource (lib "JLC_PCB") (part "0402WGF0000TCE"))
    )
    (comp (ref "Ron_a")
      (value "100k")
      (footprint "R_0402")
      (description "R - RESISTOR - SMD - 100k - 1% -  0402")
      (fields (field (name "LCSC PART #") "C25741") (field (name "Comment") "0402WGF1003TCE"))
      (libsource (lib "JLC_PCB") (part "0402WGF1003TCE"))
    )
    (comp (ref "Ron_b")
      (value "100k")
      (footprint "R_0402")
      (description "R - RESISTOR - SMD - 100k - 1% -  0402")
      (fields (field (name "LCSC PART #") "C25741") (field (name "Comment") "0402WGF1003TCE"))
      (libsource (lib "JLC_PCB") (part "0402WGF1003TCE"))
    )
    (comp (ref "Ron_c")
      (value "100k")
      (footprint "R_0402")
      (description "R - RESISTOR - SMD - 100k - 1% -  0402")
      (fields (field (name "LCSC PART #") "C25741") (field (name "Comment") "0402WGF1003TCE"))
      (libsource (lib "JLC_PCB") (part "0402WGF1003TCE"))
    )
    (comp (ref "Ron_d")
      (value "100k")
      (footprint "R_0402")
      (description "R - RESISTOR - SMD - 100k - 1% -  0402")
      (fields (field (name "LCSC PART #") "C25741") (field (name "Comment") "0402WGF1003TCE"))
      (libsource (lib "JLC_PCB") (part "0402WGF1003TCE"))
    )
    (comp (ref "R_1A_a")
      (value "47k")
      (footprint "R_0402")
      (description "R - RESISTOR - SMD - 47k - 1% - 0402")
      (fields (field (name "LCSC PART #") "C25792") (field (name "Comment") "0402WGF4702TCE"))
      (libsource (lib "JLC_PCB") (part "0402WGF4702TCE"))
    )
    (comp (ref "R_1A_b")
      (value "47k")
      (footprint "R_0402")
      (description "R - RESISTOR - SMD - 47k - 1% - 0402")
      (fields (field (name "LCSC PART #") "C25792") (field (name "Comment") "0402WGF4702TCE"))
      (libsource (lib "JLC_PCB") (part "0402WGF4702TCE"))
    )
    (comp (ref "R_1A_c")
      (value "100k")
      (footprint "R_0402")
      (description "R - RESISTOR - SMD - 100k - 1% -  0402")
      (fields (field (name "LCSC PART #") "C25741") (field (name "Comment") "0402WGF1003TCE"))
      (libsource (lib "JLC_PCB") (part "0402WGF1003TCE"))
    )
    (comp (ref "R_1B_a")
      (value "47k")
      (footprint "R_0402")
      (description "R - RESISTOR - SMD - 47k - 1% - 0402")
      (fields (field (name "LCSC PART #") "C25792") (field (name "Comment") "0402WGF4702TCE"))
      (libsource (lib "JLC_PCB") (part "0402WGF4702TCE"))
    )
    (comp (ref "R_1B_b")
      (value "47k")
      (footprint "R_0402")
      (description "R - RESISTOR - SMD - 47k - 1% - 0402")
      (fields (field (name "LCSC PART #") "C25792") (field (name "Comment") "0402WGF4702TCE"))
      (libsource (lib "JLC_PCB") (part "0402WGF4702TCE"))
    )
    (comp (ref "R_1B_c")
      (value "100k")
      (footprint "R_0402")
      (description "R - RESISTOR - SMD - 100k - 1% -  0402")
      (fields (field (name "LCSC PART #") "C25741") (field (name "Comment") "0402WGF1003TCE"))
      (libsource (lib "JLC_PCB") (part "0402WGF1003TCE"))
    )
    (comp (ref "R_LEDA_O")
      (value "0R")
      (footprint "R_0402")
      (description "R - RESISTOR - SMD - 0R - 1% - 0402")
      (fields (field (name "LCSC PART #") "C17168") (field (name "Comment") "0402WGF0000TCE"))
      (libsource (lib "JLC_PCB") (part "0402WGF0000TCE"))
    )
    (comp (ref "R_LEDB_O")
      (value "0R")
      (footprint "R_0402")
      (description "R - RESISTOR - SMD - 0R - 1% - 0402")
      (fields (field (name "LCSC PART #") "C17168") (field (name "Comment") "0402WGF0000TCE"))
      (libsource (lib "JLC_PCB") (part "0402WGF0000TCE"))
    )
    (comp (ref "U")
      (value "LT8705IUHF#TRPBF")
      (footprint "QFN-39-P0.5MM")
      (description "DC/DC Cntrlr Single-OUT Step Down/Step Up 400kHz Automotive 38-Pin QFN EP T/R")
      (fields (field (name "MP") "LT8705AIUHF#TRPBF") (field (name "LCSC PART #") "C674170"))
      (libsource (lib "JLC_PCB") (part "LT8705IUHF#TRPBF"))
    )
    (comp (ref "U1")
      (value "LM5008MMX/NOPB")
      (footprint "SOP65P490X110-8N")
      (description "U - IC - BUCK CONVERTER, ADJUSTABLE, 95V, 350mA")
      (libsource (lib "JLC_PCB") (part "LM5008MMX/NOPB"))
    )
    (comp (ref "U5V")
      (value "L78M05ABDT-TR")
      (footprint "TO-252AA")
      (description "U - IC - 5V Power Regulator")
      (fields (field (name "LCSC PART #") "C58069"))
      (libsource (lib "JLC_PCB") (part "L78M05ABDT-TR"))
    )
  )
  (nets
    (net (code "1") (name "+5VDC") (class "Default")
      (node (ref "C38") (pin "2") (pinfunction "2_2") (pintype "passive"))
      (node (ref "C42") (pin "2") (pinfunction "2_2") (pintype "passive"))
      (node (ref "R100") (pin "1") (pinfunction "1_1") (pintype "passive"))
      (node (ref "R101") (pin "1") (pinfunction "1_1") (pintype "passive"))
      (node (ref "R102") (pin "1") (pinfunction "1_1") (pintype "passive"))
      (node (ref "R103") (pin "1") (pinfunction "1_1") (pintype "passive"))
      (node (ref "R17") (pin "2") (pinfunction "2_2") (pintype "passive"))
    )
    (net (code "2") (name "/1A_GATE") (class "Default")
      (node (ref "D_1A") (pin "2") (pinfunction "A_2") (pintype "passive"))
      (node (ref "D_1A_G") (pin "1") (pinfunction "K_1") (pintype "passive"))
      (node (ref "Q_LEDA") (pin "1") (pinfunction "G_1") (pintype "passive"))
      (node (ref "R_1A_b") (pin "2") (pinfunction "2_2") (pintype "passive"))
      (node (ref "R_1A_c") (pin "2") (pinfunction "2_2") (pintype "passive"))
    )
    (net (code "3") (name "/1B_GATE") (class "Default")
      (node (ref "D_1B") (pin "2") (pinfunction "A_2") (pintype "passive"))
      (node (ref "D_1B_G") (pin "1") (pinfunction "K_1") (pintype "passive"))
      (node (ref "R_1B_b") (pin "2") (pinfunction "2_2") (pintype "passive"))
      (node (ref "R_1B_c") (pin "2") (pinfunction "2_2") (pintype "passive"))
    )
    (net (code "4") (name "/A1_N") (class "Default")
      (node (ref "RA1_P") (pin "2") (pinfunction "2_2") (pintype "passive"))
    )
    (net (code "5") (name "/A1_P") (class "Default")
      (node (ref "RA1_N") (pin "2") (pinfunction "2_2") (pintype "passive"))
    )
    (net (code "6") (name "/A2_N") (class "Default")
      (node (ref "RB1_N") (pin "2") (pinfunction "2_2") (pintype "passive"))
    )
    (net (code "7") (name "/A2_P") (class "Default")
      (node (ref "RB1_P") (pin "2") (pinfunction "2_2") (pintype "passive"))
    )
    (net (code "8") (name "/AGND") (class "Default")
      (node (ref "NT2") (pin "1") (pinfunction "1_1") (pintype "passive"))
    )
    (net (code "9") (name "/GND_OUT") (class "Default")
      (node (ref "J_OUT") (pin "MINUS") (pinfunction "-_MINUS") (pintype "passive"))
    )
    (net (code "10") (name "/HO_A") (class "Default")
      (node (ref "D3") (pin "1") (pinfunction "K_1") (pintype "passive"))
      (node (ref "R18") (pin "1") (pinfunction "1_1") (pintype "passive"))
      (node (ref "R18_a") (pin "1") (pinfunction "1_1") (pintype "passive"))
    )
    (net (code "11") (name "/HO_B") (class "Default")
      (node (ref "D4") (pin "1") (pinfunction "K_1") (pintype "passive"))
      (node (ref "R19") (pin "2") (pinfunction "2_2") (pintype "passive"))
      (node (ref "R19_a") (pin "2") (pinfunction "2_2") (pintype "passive"))
    )
    (net (code "12") (name "/HS_A") (class "Default")
      (node (ref "C18") (pin "2") (pinfunction "2_2") (pintype "passive"))
      (node (ref "D12") (pin "1") (pinfunction "K_1") (pintype "passive"))
      (node (ref "D13") (pin "2") (pinfunction "A_2") (pintype "passive"))
      (node (ref "L1") (pin "1") (pinfunction "1_1") (pintype "passive"))
      (node (ref "L10") (pin "1") (pinfunction "1_1") (pintype "passive"))
      (node (ref "L11") (pin "1") (pinfunction "1_1") (pintype "passive"))
      (node (ref "L12") (pin "1") (pinfunction "1_1") (pintype "passive"))
      (node (ref "L2") (pin "1") (pinfunction "1_1") (pintype "passive"))
      (node (ref "L3") (pin "1") (pinfunction "1_1") (pintype "passive"))
      (node (ref "L4") (pin "1") (pinfunction "1_1") (pintype "passive"))
      (node (ref "L5") (pin "1") (pinfunction "1_1") (pintype "passive"))
      (node (ref "L6") (pin "1") (pinfunction "1_1") (pintype "passive"))
      (node (ref "L7") (pin "1") (pinfunction "1_1") (pintype "passive"))
      (node (ref "L8") (pin "1") (pinfunction "1_1") (pintype "passive"))
      (node (ref "L9") (pin "1") (pinfunction "1_1") (pintype "passive"))
      (node (ref "Q1") (pin "3") (pinfunction "S_3") (pintype "passive"))
      (node (ref "Q3") (pin "2") (pinfunction "D_2") (pintype "passive"))
      (node (ref "R4") (pin "1") (pinfunction "1_1") (pintype "passive"))
    )
    (net (code "13") (name "/HS_B") (class "Default")
      (node (ref "C19") (pin "2") (pinfunction "2_2") (pintype "passive"))
      (node (ref "D7") (pin "2") (pinfunction "A_2") (pintype "passive"))
      (node (ref "D9") (pin "1") (pinfunction "K_1") (pintype "passive"))
      (node (ref "L1") (pin "2") (pinfunction "2_2") (pintype "passive"))
      (node (ref "L10") (pin "2") (pinfunction "2_2") (pintype "passive"))
      (node (ref "L11") (pin "2") (pinfunction "2_2") (pintype "passive"))
      (node (ref "L12") (pin "2") (pinfunction "2_2") (pintype "passive"))
      (node (ref "L2") (pin "2") (pinfunction "2_2") (pintype "passive"))
      (node (ref "L3") (pin "2") (pinfunction "2_2") (pintype "passive"))
      (node (ref "L4") (pin "2") (pinfunction "2_2") (pintype "passive"))
      (node (ref "L5") (pin "2") (pinfunction "2_2") (pintype "passive"))
      (node (ref "L6") (pin "2") (pinfunction "2_2") (pintype "passive"))
      (node (ref "L7") (pin "2") (pinfunction "2_2") (pintype "passive"))
      (node (ref "L8") (pin "2") (pinfunction "2_2") (pintype "passive"))
      (node (ref "L9") (pin "2") (pinfunction "2_2") (pintype "passive"))
      (node (ref "Q2") (pin "3") (pinfunction "S_3") (pintype "passive"))
      (node (ref "Q4") (pin "2") (pinfunction "D_2") (pintype "passive"))
      (node (ref "R3") (pin "2") (pinfunction "2_2") (pintype "passive"))
    )
    (net (code "14") (name "/LED_A") (class "Default")
      (node (ref "J1") (pin "9") (pinfunction "9_9") (pintype "passive"))
      (node (ref "J2") (pin "11") (pinfunction "11_11") (pintype "passive"))
      (node (ref "R_LEDB_O") (pin "2") (pinfunction "2_2") (pintype "passive"))
    )
    (net (code "15") (name "/LED_B") (class "Default")
      (node (ref "J1") (pin "11") (pinfunction "11_11") (pintype "passive"))
      (node (ref "J2") (pin "9") (pinfunction "9_9") (pintype "passive"))
      (node (ref "R_LEDA_O") (pin "2") (pinfunction "2_2") (pintype "passive"))
    )
    (net (code "16") (name "/LED_VSS") (class "Default")
      (node (ref "Q_LEDA") (pin "2") (pinfunction "S_2") (pintype "passive"))
      (node (ref "Q_LEDB") (pin "2") (pinfunction "S_2") (pintype "passive"))
      (node (ref "Q_LEDVSS") (pin "3") (pinfunction "D_3") (pintype "passive"))
    )
    (net (code "17") (name "/LO_A") (class "Default")
      (node (ref "D5") (pin "1") (pinfunction "K_1") (pintype "passive"))
      (node (ref "R32") (pin "1") (pinfunction "1_1") (pintype "passive"))
      (node (ref "R32_a") (pin "1") (pinfunction "1_1") (pintype "passive"))
    )
    (net (code "18") (name "/LO_B") (class "Default")
      (node (ref "D6") (pin "1") (pinfunction "K_1") (pintype "passive"))
      (node (ref "R33") (pin "2") (pinfunction "2_2") (pintype "passive"))
      (node (ref "R33_a") (pin "2") (pinfunction "2_2") (pintype "passive"))
    )
    (net (code "19") (name "/PAN_DET") (class "Default")
      (node (ref "D_1A") (pin "1") (pinfunction "K_1") (pintype "passive"))
      (node (ref "D_1B") (pin "1") (pinfunction "K_1") (pintype "passive"))
      (node (ref "Q_LEDVSS") (pin "1") (pinfunction "G_1") (pintype "passive"))
    )
    (net (code "20") (name "/SOL_1A") (class "Default")
      (node (ref "D1_a") (pin "2") (pinfunction "A_2") (pintype "passive"))
      (node (ref "D1_b") (pin "2") (pinfunction "A_2") (pintype "passive"))
      (node (ref "D1_c") (pin "2") (pinfunction "A_2") (pintype "passive"))
      (node (ref "D1_d") (pin "2") (pinfunction "A_2") (pintype "passive"))
      (node (ref "D1_e") (pin "2") (pinfunction "A_2") (pintype "passive"))
      (node (ref "D1_f") (pin "2") (pinfunction "A_2") (pintype "passive"))
      (node (ref "D3_a") (pin "1") (pinfunction "K_1") (pintype "passive"))
      (node (ref "D3_b") (pin "1") (pinfunction "K_1") (pintype "passive"))
      (node (ref "D3_c") (pin "1") (pinfunction "K_1") (pintype "passive"))
      (node (ref "D3_d") (pin "1") (pinfunction "K_1") (pintype "passive"))
      (node (ref "D3_e") (pin "1") (pinfunction "K_1") (pintype "passive"))
      (node (ref "D3_f") (pin "1") (pinfunction "K_1") (pintype "passive"))
      (node (ref "J1") (pin "1") (pinfunction "1_1") (pintype "passive"))
      (node (ref "J1") (pin "2") (pinfunction "2_2") (pintype "passive"))
      (node (ref "J1") (pin "3") (pinfunction "3_3") (pintype "passive"))
      (node (ref "J1") (pin "4") (pinfunction "4_4") (pintype "passive"))
      (node (ref "J1") (pin "5") (pinfunction "5_5") (pintype "passive"))
      (node (ref "J1") (pin "6") (pinfunction "6_6") (pintype "passive"))
      (node (ref "J1") (pin "7") (pinfunction "7_7") (pintype "passive"))
      (node (ref "J1") (pin "8") (pinfunction "8_8") (pintype "passive"))
      (node (ref "J_IN") (pin "PLUS") (pinfunction "+_PLUS") (pintype "passive"))
      (node (ref "R_1A_a") (pin "1") (pinfunction "1_1") (pintype "passive"))
    )
    (net (code "21") (name "/SOL_1B") (class "Default")
      (node (ref "D2_a") (pin "2") (pinfunction "A_2") (pintype "passive"))
      (node (ref "D2_b") (pin "2") (pinfunction "A_2") (pintype "passive"))
      (node (ref "D2_c") (pin "2") (pinfunction "A_2") (pintype "passive"))
      (node (ref "D2_d") (pin "2") (pinfunction "A_2") (pintype "passive"))
      (node (ref "D2_e") (pin "2") (pinfunction "A_2") (pintype "passive"))
      (node (ref "D2_f") (pin "2") (pinfunction "A_2") (pintype "passive"))
      (node (ref "D4_a") (pin "1") (pinfunction "K_1") (pintype "passive"))
      (node (ref "D4_b") (pin "1") (pinfunction "K_1") (pintype "passive"))
      (node (ref "D4_c") (pin "1") (pinfunction "K_1") (pintype "passive"))
      (node (ref "D4_d") (pin "1") (pinfunction "K_1") (pintype "passive"))
      (node (ref "D4_e") (pin "1") (pinfunction "K_1") (pintype "passive"))
      (node (ref "D4_f") (pin "1") (pinfunction "K_1") (pintype "passive"))
      (node (ref "J2") (pin "1") (pinfunction "1_1") (pintype "passive"))
      (node (ref "J2") (pin "2") (pinfunction "2_2") (pintype "passive"))
      (node (ref "J2") (pin "3") (pinfunction "3_3") (pintype "passive"))
      (node (ref "J2") (pin "4") (pinfunction "4_4") (pintype "passive"))
      (node (ref "J2") (pin "5") (pinfunction "5_5") (pintype "passive"))
      (node (ref "J2") (pin "6") (pinfunction "6_6") (pintype "passive"))
      (node (ref "J2") (pin "7") (pinfunction "7_7") (pintype "passive"))
      (node (ref "J2") (pin "8") (pinfunction "8_8") (pintype "passive"))
      (node (ref "J_IN") (pin "MINUS") (pinfunction "-_MINUS") (pintype "passive"))
      (node (ref "R_1B_a") (pin "1") (pinfunction "1_1") (pintype "passive"))
    )
    (net (code "22") (name "/VOUT_N") (class "Default")
      (node (ref "J_OUT") (pin "PLUS") (pinfunction "+_PLUS") (pintype "passive"))
      (node (ref "R10") (pin "2") (pinfunction "2_2") (pintype "passive"))
      (node (ref "RA1_N") (pin "1") (pinfunction "1_1") (pintype "passive"))
    )
    (net (code "23") (name "10VDC") (class "Default")
      (node (ref "C23_a") (pin "1") (pinfunction "1_1") (pintype "passive"))
      (node (ref "C23_b") (pin "1") (pinfunction "1_1") (pintype "passive"))
      (node (ref "C23_c") (pin "1") (pinfunction "1_1") (pintype "passive"))
      (node (ref "C23_d") (pin "1") (pinfunction "1_1") (pintype "passive"))
      (node (ref "C23_e") (pin "1") (pinfunction "1_1") (pintype "passive"))
      (node (ref "C23_f") (pin "1") (pinfunction "1_1") (pintype "passive"))
      (node (ref "C23_g") (pin "1") (pinfunction "1_1") (pintype "passive"))
      (node (ref "C24") (pin "2") (pinfunction "2_2") (pintype "passive"))
      (node (ref "C40") (pin "2") (pinfunction "2_2") (pintype "passive"))
      (node (ref "L0") (pin "2") (pinfunction "2_2") (pintype "passive"))
      (node (ref "R9") (pin "1") (pinfunction "1_1") (pintype "passive"))
      (node (ref "U5V") (pin "1") (pinfunction "VIN_1") (pintype "input"))
    )
    (net (code "24") (name "GND") (class "Default")
      (node (ref "C15") (pin "2") (pinfunction "2_2") (pintype "passive"))
      (node (ref "C21") (pin "1") (pinfunction "1_1") (pintype "passive"))
      (node (ref "C22") (pin "1") (pinfunction "1_1") (pintype "passive"))
      (node (ref "C23_a") (pin "2") (pinfunction "2_2") (pintype "passive"))
      (node (ref "C23_b") (pin "2") (pinfunction "2_2") (pintype "passive"))
      (node (ref "C23_c") (pin "2") (pinfunction "2_2") (pintype "passive"))
      (node (ref "C23_d") (pin "2") (pinfunction "2_2") (pintype "passive"))
      (node (ref "C23_e") (pin "2") (pinfunction "2_2") (pintype "passive"))
      (node (ref "C23_f") (pin "2") (pinfunction "2_2") (pintype "passive"))
      (node (ref "C23_g") (pin "2") (pinfunction "2_2") (pintype "passive"))
      (node (ref "C26") (pin "1") (pinfunction "1_1") (pintype "passive"))
      (node (ref "C38") (pin "1") (pinfunction "1_1") (pintype "passive"))
      (node (ref "C40") (pin "1") (pinfunction "1_1") (pintype "passive"))
      (node (ref "C42") (pin "1") (pinfunction "1_1") (pintype "passive"))
      (node (ref "C64") (pin "1") (pinfunction "1_1") (pintype "passive"))
      (node (ref "D2") (pin "2") (pinfunction "A_2") (pintype "passive"))
      (node (ref "D_1A_G") (pin "2") (pinfunction "A_2") (pintype "passive"))
      (node (ref "D_1B_G") (pin "2") (pinfunction "A_2") (pintype "passive"))
      (node (ref "NT2") (pin "2") (pinfunction "2_2") (pintype "passive"))
      (node (ref "Q_LEDVSS") (pin "2") (pinfunction "S_2") (pintype "passive"))
      (node (ref "R15") (pin "1") (pinfunction "1_1") (pintype "passive"))
      (node (ref "R5_a") (pin "1") (pinfunction "1_1") (pintype "passive"))
      (node (ref "R_1A_c") (pin "1") (pinfunction "1_1") (pintype "passive"))
      (node (ref "R_1B_c") (pin "1") (pinfunction "1_1") (pintype "passive"))
      (node (ref "U1") (pin "4") (pinfunction "RTN_4") (pintype "bidirectional"))
      (node (ref "U5V") (pin "2") (pinfunction "GND_2") (pintype "power_in"))
    )
    (net (code "25") (name "GND_IN") (class "Default")
      (node (ref "D3_a") (pin "2") (pinfunction "A_2") (pintype "passive"))
      (node (ref "D3_b") (pin "2") (pinfunction "A_2") (pintype "passive"))
      (node (ref "D3_c") (pin "2") (pinfunction "A_2") (pintype "passive"))
      (node (ref "D3_d") (pin "2") (pinfunction "A_2") (pintype "passive"))
      (node (ref "D3_e") (pin "2") (pinfunction "A_2") (pintype "passive"))
      (node (ref "D3_f") (pin "2") (pinfunction "A_2") (pintype "passive"))
      (node (ref "D4_a") (pin "2") (pinfunction "A_2") (pintype "passive"))
      (node (ref "D4_b") (pin "2") (pinfunction "A_2") (pintype "passive"))
      (node (ref "D4_c") (pin "2") (pinfunction "A_2") (pintype "passive"))
      (node (ref "D4_d") (pin "2") (pinfunction "A_2") (pintype "passive"))
      (node (ref "D4_e") (pin "2") (pinfunction "A_2") (pintype "passive"))
      (node (ref "D4_f") (pin "2") (pinfunction "A_2") (pintype "passive"))
      (node (ref "D_CLAMP_18") (pin "2") (pinfunction "A_2") (pintype "passive"))
    )
    (net (code "26") (name "Net-(D2-K)") (class "Default")
      (node (ref "C17") (pin "2") (pinfunction "2_2") (pintype "passive"))
      (node (ref "D2") (pin "1") (pinfunction "K_1") (pintype "passive"))
      (node (ref "L0") (pin "1") (pinfunction "1_1") (pintype "passive"))
      (node (ref "U1") (pin "1") (pinfunction "SW_1") (pintype "bidirectional"))
    )
    (net (code "27") (name "Net-(D3-A)") (class "Default")
      (node (ref "D3") (pin "2") (pinfunction "A_2") (pintype "passive"))
      (node (ref "Q1") (pin "1") (pinfunction "G_1") (pintype "passive"))
      (node (ref "R18") (pin "2") (pinfunction "2_2") (pintype "passive"))
      (node (ref "R18_a") (pin "2") (pinfunction "2_2") (pintype "passive"))
      (node (ref "R4") (pin "2") (pinfunction "2_2") (pintype "passive"))
    )
    (net (code "28") (name "Net-(D4-A)") (class "Default")
      (node (ref "D4") (pin "2") (pinfunction "A_2") (pintype "passive"))
      (node (ref "Q2") (pin "1") (pinfunction "G_1") (pintype "passive"))
      (node (ref "R19") (pin "1") (pinfunction "1_1") (pintype "passive"))
      (node (ref "R19_a") (pin "1") (pinfunction "1_1") (pintype "passive"))
      (node (ref "R3") (pin "1") (pinfunction "1_1") (pintype "passive"))
    )
    (net (code "29") (name "Net-(D5-A)") (class "Default")
      (node (ref "D5") (pin "2") (pinfunction "A_2") (pintype "passive"))
      (node (ref "Q3") (pin "1") (pinfunction "G_1") (pintype "passive"))
      (node (ref "R22") (pin "2") (pinfunction "2_2") (pintype "passive"))
      (node (ref "R32") (pin "2") (pinfunction "2_2") (pintype "passive"))
      (node (ref "R32_a") (pin "2") (pinfunction "2_2") (pintype "passive"))
    )
    (net (code "30") (name "Net-(D6-A)") (class "Default")
      (node (ref "D6") (pin "2") (pinfunction "A_2") (pintype "passive"))
      (node (ref "Q4") (pin "1") (pinfunction "G_1") (pintype "passive"))
      (node (ref "R23") (pin "1") (pinfunction "1_1") (pintype "passive"))
      (node (ref "R33") (pin "1") (pinfunction "1_1") (pintype "passive"))
      (node (ref "R33_a") (pin "1") (pinfunction "1_1") (pintype "passive"))
    )
    (net (code "31") (name "Net-(D14-A)") (class "Default")
      (node (ref "C19") (pin "1") (pinfunction "1_1") (pintype "passive"))
      (node (ref "D14") (pin "2") (pinfunction "A_2") (pintype "passive"))
      (node (ref "R14") (pin "2") (pinfunction "2_2") (pintype "passive"))
    )
    (net (code "32") (name "Net-(D15-A)") (class "Default")
      (node (ref "C18") (pin "1") (pinfunction "1_1") (pintype "passive"))
      (node (ref "D15") (pin "2") (pinfunction "A_2") (pintype "passive"))
      (node (ref "R11") (pin "2") (pinfunction "2_2") (pintype "passive"))
    )
    (net (code "33") (name "Net-(D_CLAMP_1-A)") (class "Default")
      (node (ref "D_CLAMP_1") (pin "2") (pinfunction "A_2") (pintype "passive"))
      (node (ref "D_CLAMP_2") (pin "1") (pinfunction "K_1") (pintype "passive"))
    )
    (net (code "34") (name "Net-(D_CLAMP_2-A)") (class "Default")
      (node (ref "D_CLAMP_2") (pin "2") (pinfunction "A_2") (pintype "passive"))
      (node (ref "D_CLAMP_3") (pin "1") (pinfunction "K_1") (pintype "passive"))
    )
    (net (code "35") (name "Net-(D_CLAMP_3-A)") (class "Default")
      (node (ref "D_CLAMP_3") (pin "2") (pinfunction "A_2") (pintype "passive"))
      (node (ref "D_CLAMP_4") (pin "1") (pinfunction "K_1") (pintype "passive"))
    )
    (net (code "36") (name "Net-(D_CLAMP_4-A)") (class "Default")
      (node (ref "D_CLAMP_4") (pin "2") (pinfunction "A_2") (pintype "passive"))
      (node (ref "D_CLAMP_5") (pin "1") (pinfunction "K_1") (pintype "passive"))
    )
    (net (code "37") (name "Net-(D_CLAMP_5-A)") (class "Default")
      (node (ref "D_CLAMP_5") (pin "2") (pinfunction "A_2") (pintype "passive"))
      (node (ref "D_CLAMP_6") (pin "1") (pinfunction "K_1") (pintype "passive"))
    )
    (net (code "38") (name "Net-(D_CLAMP_6-A)") (class "Default")
      (node (ref "D_CLAMP_6") (pin "2") (pinfunction "A_2") (pintype "passive"))
      (node (ref "D_CLAMP_7") (pin "1") (pinfunction "K_1") (pintype "passive"))
    )
    (net (code "39") (name "Net-(D_CLAMP_7-A)") (class "Default")
      (node (ref "D_CLAMP_7") (pin "2") (pinfunction "A_2") (pintype "passive"))
      (node (ref "D_CLAMP_8") (pin "1") (pinfunction "K_1") (pintype "passive"))
      (node (ref "R16") (pin "2") (pinfunction "2_2") (pintype "passive"))
    )
    (net (code "40") (name "Net-(D_CLAMP_8-A)") (class "Default")
      (node (ref "D_CLAMP_8") (pin "2") (pinfunction "A_2") (pintype "passive"))
      (node (ref "D_CLAMP_9") (pin "1") (pinfunction "K_1") (pintype "passive"))
    )
    (net (code "41") (name "Net-(D_CLAMP_10-A)") (class "Default")
      (node (ref "D_CLAMP_10") (pin "2") (pinfunction "A_2") (pintype "passive"))
      (node (ref "D_CLAMP_11") (pin "1") (pinfunction "K_1") (pintype "passive"))
    )
    (net (code "42") (name "Net-(D_CLAMP_10-K)") (class "Default")
      (node (ref "D_CLAMP_10") (pin "1") (pinfunction "K_1") (pintype "passive"))
      (node (ref "D_CLAMP_9") (pin "2") (pinfunction "A_2") (pintype "passive"))
      (node (ref "R16") (pin "1") (pinfunction "1_1") (pintype "passive"))
    )
    (net (code "43") (name "Net-(D_CLAMP_11-A)") (class "Default")
      (node (ref "D_CLAMP_11") (pin "2") (pinfunction "A_2") (pintype "passive"))
      (node (ref "D_CLAMP_12") (pin "1") (pinfunction "K_1") (pintype "passive"))
    )
    (net (code "44") (name "Net-(D_CLAMP_12-A)") (class "Default")
      (node (ref "D_CLAMP_12") (pin "2") (pinfunction "A_2") (pintype "passive"))
      (node (ref "D_CLAMP_13") (pin "1") (pinfunction "K_1") (pintype "passive"))
    )
    (net (code "45") (name "Net-(D_CLAMP_13-A)") (class "Default")
      (node (ref "D_CLAMP_13") (pin "2") (pinfunction "A_2") (pintype "passive"))
      (node (ref "D_CLAMP_14") (pin "1") (pinfunction "K_1") (pintype "passive"))
    )
    (net (code "46") (name "Net-(D_CLAMP_14-A)") (class "Default")
      (node (ref "D_CLAMP_14") (pin "2") (pinfunction "A_2") (pintype "passive"))
      (node (ref "D_CLAMP_15") (pin "1") (pinfunction "K_1") (pintype "passive"))
    )
    (net (code "47") (name "Net-(D_CLAMP_15-A)") (class "Default")
      (node (ref "D_CLAMP_15") (pin "2") (pinfunction "A_2") (pintype "passive"))
      (node (ref "D_CLAMP_16") (pin "1") (pinfunction "K_1") (pintype "passive"))
    )
    (net (code "48") (name "Net-(D_CLAMP_16-A)") (class "Default")
      (node (ref "D_CLAMP_16") (pin "2") (pinfunction "A_2") (pintype "passive"))
      (node (ref "D_CLAMP_17") (pin "1") (pinfunction "K_1") (pintype "passive"))
    )
    (net (code "49") (name "Net-(D_CLAMP_17-A)") (class "Default")
      (node (ref "D_CLAMP_17") (pin "2") (pinfunction "A_2") (pintype "passive"))
      (node (ref "D_CLAMP_18") (pin "1") (pinfunction "K_1") (pintype "passive"))
    )
    (net (code "50") (name "Net-(J1-Pad10)") (class "Default")
      (node (ref "J1") (pin "10") (pinfunction "10_10") (pintype "passive"))
      (node (ref "R101") (pin "2") (pinfunction "2_2") (pintype "passive"))
    )
    (net (code "51") (name "Net-(J1-Pad12)") (class "Default")
      (node (ref "J1") (pin "12") (pinfunction "12_12") (pintype "passive"))
      (node (ref "R100") (pin "2") (pinfunction "2_2") (pintype "passive"))
    )
    (net (code "52") (name "Net-(J1-SHIELD-PadS1)") (class "Default")
      (node (ref "J1") (pin "S1") (pinfunction "SHIELD_S1") (pintype "passive"))
      (node (ref "J1") (pin "S2") (pinfunction "SHIELD_S2") (pintype "passive"))
    )
    (net (code "53") (name "Net-(J2-Pad10)") (class "Default")
      (node (ref "J2") (pin "10") (pinfunction "10_10") (pintype "passive"))
      (node (ref "R102") (pin "2") (pinfunction "2_2") (pintype "passive"))
    )
    (net (code "54") (name "Net-(J2-Pad12)") (class "Default")
      (node (ref "J2") (pin "12") (pinfunction "12_12") (pintype "passive"))
      (node (ref "R103") (pin "2") (pinfunction "2_2") (pintype "passive"))
    )
    (net (code "55") (name "Net-(J2-SHIELD-PadS1)") (class "Default")
      (node (ref "J2") (pin "S1") (pinfunction "SHIELD_S1") (pintype "passive"))
      (node (ref "J2") (pin "S2") (pinfunction "SHIELD_S2") (pintype "passive"))
    )
    (net (code "56") (name "Net-(Q_LEDA-D)") (class "Default")
      (node (ref "Q_LEDA") (pin "3") (pinfunction "D_3") (pintype "passive"))
      (node (ref "Q_LEDB") (pin "1") (pinfunction "G_1") (pintype "passive"))
      (node (ref "R_LEDB_O") (pin "1") (pinfunction "1_1") (pintype "passive"))
    )
    (net (code "57") (name "Net-(Q_LEDB-D)") (class "Default")
      (node (ref "Q_LEDB") (pin "3") (pinfunction "D_3") (pintype "passive"))
      (node (ref "R_LEDA_O") (pin "1") (pinfunction "1_1") (pintype "passive"))
    )
    (net (code "58") (name "Net-(R5-Pad1)") (class "Default")
      (node (ref "R5") (pin "1") (pinfunction "1_1") (pintype "passive"))
      (node (ref "R5_a") (pin "2") (pinfunction "2_2") (pintype "passive"))
    )
    (net (code "59") (name "Net-(R_1A_a-Pad2)") (class "Default")
      (node (ref "R_1A_a") (pin "2") (pinfunction "2_2") (pintype "passive"))
      (node (ref "R_1A_b") (pin "1") (pinfunction "1_1") (pintype "passive"))
    )
    (net (code "60") (name "Net-(R_1B_a-Pad2)") (class "Default")
      (node (ref "R_1B_a") (pin "2") (pinfunction "2_2") (pintype "passive"))
      (node (ref "R_1B_b") (pin "1") (pinfunction "1_1") (pintype "passive"))
    )
    (net (code "61") (name "Net-(Ron_a-Pad1)") (class "Default")
      (node (ref "Ron_a") (pin "1") (pinfunction "1_1") (pintype "passive"))
      (node (ref "Ron_b") (pin "1") (pinfunction "1_1") (pintype "passive"))
    )
    (net (code "62") (name "Net-(Ron_b-Pad2)") (class "Default")
      (node (ref "Ron_b") (pin "2") (pinfunction "2_2") (pintype "passive"))
      (node (ref "Ron_c") (pin "2") (pinfunction "2_2") (pintype "passive"))
      (node (ref "Ron_d") (pin "2") (pinfunction "2_2") (pintype "passive"))
    )
    (net (code "63") (name "Net-(U1-BST)") (class "Default")
      (node (ref "C17") (pin "1") (pinfunction "1_1") (pintype "passive"))
      (node (ref "U1") (pin "2") (pinfunction "BST_2") (pintype "bidirectional"))
    )
    (net (code "64") (name "Net-(U1-FB)") (class "Default")
      (node (ref "C24") (pin "1") (pinfunction "1_1") (pintype "passive"))
      (node (ref "R15") (pin "2") (pinfunction "2_2") (pintype "passive"))
      (node (ref "R9") (pin "2") (pinfunction "2_2") (pintype "passive"))
      (node (ref "U1") (pin "5") (pinfunction "FB_5") (pintype "bidirectional"))
    )
    (net (code "65") (name "Net-(U1-RCL)") (class "Default")
      (node (ref "R5") (pin "2") (pinfunction "2_2") (pintype "passive"))
      (node (ref "U1") (pin "3") (pinfunction "RCL_3") (pintype "input"))
    )
    (net (code "66") (name "Net-(U1-RT{slash}SD)") (class "Default")
      (node (ref "Ron_a") (pin "2") (pinfunction "2_2") (pintype "passive"))
      (node (ref "U1") (pin "6") (pinfunction "RT/SD_6") (pintype "input"))
    )
    (net (code "67") (name "Net-(U1-VCC)") (class "Default")
      (node (ref "C15") (pin "1") (pinfunction "1_1") (pintype "passive"))
      (node (ref "U1") (pin "7") (pinfunction "VCC_7") (pintype "power_in"))
    )
    (net (code "68") (name "Net-(U5V-Vout)") (class "Default")
      (node (ref "R17") (pin "1") (pinfunction "1_1") (pintype "passive"))
      (node (ref "U5V") (pin "3") (pinfunction "Vout_3") (pintype "output"))
    )
    (net (code "69") (name "PGND") (class "Default")
      (node (ref "C1") (pin "1") (pinfunction "1_1") (pintype "passive"))
      (node (ref "C10") (pin "1") (pinfunction "1_1") (pintype "passive"))
      (node (ref "C11") (pin "1") (pinfunction "1_1") (pintype "passive"))
      (node (ref "C12") (pin "1") (pinfunction "1_1") (pintype "passive"))
      (node (ref "C13") (pin "1") (pinfunction "1_1") (pintype "passive"))
      (node (ref "C16") (pin "1") (pinfunction "1_1") (pintype "passive"))
      (node (ref "C20") (pin "1") (pinfunction "1_1") (pintype "passive"))
      (node (ref "C25") (pin "1") (pinfunction "1_1") (pintype "passive"))
      (node (ref "C27") (pin "1") (pinfunction "1_1") (pintype "passive"))
      (node (ref "C28") (pin "1") (pinfunction "1_1") (pintype "passive"))
      (node (ref "C30") (pin "1") (pinfunction "1_1") (pintype "passive"))
      (node (ref "C36") (pin "1") (pinfunction "1_1") (pintype "passive"))
      (node (ref "C4") (pin "1") (pinfunction "1_1") (pintype "passive"))
      (node (ref "C41") (pin "1") (pinfunction "1_1") (pintype "passive"))
      (node (ref "C44") (pin "1") (pinfunction "1_1") (pintype "passive"))
      (node (ref "C45") (pin "1") (pinfunction "1_1") (pintype "passive"))
      (node (ref "C47") (pin "1") (pinfunction "1_1") (pintype "passive"))
      (node (ref "C5") (pin "1") (pinfunction "1_1") (pintype "passive"))
      (node (ref "C6") (pin "1") (pinfunction "1_1") (pintype "passive"))
      (node (ref "C7") (pin "1") (pinfunction "1_1") (pintype "passive"))
      (node (ref "C70") (pin "1") (pinfunction "1_1") (pintype "passive"))
      (node (ref "C72") (pin "1") (pinfunction "1_1") (pintype "passive"))
      (node (ref "C8") (pin "1") (pinfunction "1_1") (pintype "passive"))
      (node (ref "C9") (pin "1") (pinfunction "1_1") (pintype "passive"))
      (node (ref "D12") (pin "2") (pinfunction "A_2") (pintype "passive"))
      (node (ref "D14") (pin "1") (pinfunction "K_1") (pintype "passive"))
      (node (ref "D15") (pin "1") (pinfunction "K_1") (pintype "passive"))
      (node (ref "D9") (pin "2") (pinfunction "A_2") (pintype "passive"))
      (node (ref "Q3") (pin "3") (pinfunction "S_3") (pintype "passive"))
      (node (ref "Q4") (pin "3") (pinfunction "S_3") (pintype "passive"))
      (node (ref "R11") (pin "1") (pinfunction "1_1") (pintype "passive"))
      (node (ref "R14") (pin "1") (pinfunction "1_1") (pintype "passive"))
      (node (ref "R22") (pin "1") (pinfunction "1_1") (pintype "passive"))
      (node (ref "R23") (pin "2") (pinfunction "2_2") (pintype "passive"))
    )
    (net (code "70") (name "VIN_N") (class "Default")
      (node (ref "C10") (pin "2") (pinfunction "2_2") (pintype "passive"))
      (node (ref "C11") (pin "2") (pinfunction "2_2") (pintype "passive"))
      (node (ref "C12") (pin "2") (pinfunction "2_2") (pintype "passive"))
      (node (ref "C13") (pin "2") (pinfunction "2_2") (pintype "passive"))
      (node (ref "C4") (pin "2") (pinfunction "2_2") (pintype "passive"))
      (node (ref "C5") (pin "2") (pinfunction "2_2") (pintype "passive"))
      (node (ref "C6") (pin "2") (pinfunction "2_2") (pintype "passive"))
      (node (ref "C7") (pin "2") (pinfunction "2_2") (pintype "passive"))
      (node (ref "C70") (pin "2") (pinfunction "2_2") (pintype "passive"))
      (node (ref "C72") (pin "2") (pinfunction "2_2") (pintype "passive"))
      (node (ref "C8") (pin "2") (pinfunction "2_2") (pintype "passive"))
      (node (ref "C9") (pin "2") (pinfunction "2_2") (pintype "passive"))
      (node (ref "D13") (pin "1") (pinfunction "K_1") (pintype "passive"))
      (node (ref "Q1") (pin "2") (pinfunction "D_2") (pintype "passive"))
      (node (ref "R1") (pin "1") (pinfunction "1_1") (pintype "passive"))
      (node (ref "RB1_P") (pin "1") (pinfunction "1_1") (pintype "passive"))
    )
    (net (code "71") (name "VIN_P") (class "Default")
      (node (ref "C21") (pin "2") (pinfunction "2_2") (pintype "passive"))
      (node (ref "C22") (pin "2") (pinfunction "2_2") (pintype "passive"))
      (node (ref "C26") (pin "2") (pinfunction "2_2") (pintype "passive"))
      (node (ref "C64") (pin "2") (pinfunction "2_2") (pintype "passive"))
      (node (ref "D1_a") (pin "1") (pinfunction "K_1") (pintype "passive"))
      (node (ref "D1_b") (pin "1") (pinfunction "K_1") (pintype "passive"))
      (node (ref "D1_c") (pin "1") (pinfunction "K_1") (pintype "passive"))
      (node (ref "D1_d") (pin "1") (pinfunction "K_1") (pintype "passive"))
      (node (ref "D1_e") (pin "1") (pinfunction "K_1") (pintype "passive"))
      (node (ref "D1_f") (pin "1") (pinfunction "K_1") (pintype "passive"))
      (node (ref "D2_a") (pin "1") (pinfunction "K_1") (pintype "passive"))
      (node (ref "D2_b") (pin "1") (pinfunction "K_1") (pintype "passive"))
      (node (ref "D2_c") (pin "1") (pinfunction "K_1") (pintype "passive"))
      (node (ref "D2_d") (pin "1") (pinfunction "K_1") (pintype "passive"))
      (node (ref "D2_e") (pin "1") (pinfunction "K_1") (pintype "passive"))
      (node (ref "D2_f") (pin "1") (pinfunction "K_1") (pintype "passive"))
      (node (ref "D_CLAMP_1") (pin "1") (pinfunction "K_1") (pintype "passive"))
      (node (ref "R1") (pin "2") (pinfunction "2_2") (pintype "passive"))
      (node (ref "RB1_N") (pin "1") (pinfunction "1_1") (pintype "passive"))
      (node (ref "Ron_c") (pin "1") (pinfunction "1_1") (pintype "passive"))
      (node (ref "Ron_d") (pin "1") (pinfunction "1_1") (pintype "passive"))
      (node (ref "U1") (pin "8") (pinfunction "VIN_8") (pintype "input"))
    )
    (net (code "72") (name "VOUT_P") (class "Default")
      (node (ref "C1") (pin "2") (pinfunction "2_2") (pintype "passive"))
      (node (ref "C16") (pin "2") (pinfunction "2_2") (pintype "passive"))
      (node (ref "C20") (pin "2") (pinfunction "2_2") (pintype "passive"))
      (node (ref "C25") (pin "2") (pinfunction "2_2") (pintype "passive"))
      (node (ref "C27") (pin "2") (pinfunction "2_2") (pintype "passive"))
      (node (ref "C28") (pin "2") (pinfunction "2_2") (pintype "passive"))
      (node (ref "C30") (pin "2") (pinfunction "2_2") (pintype "passive"))
      (node (ref "C36") (pin "2") (pinfunction "2_2") (pintype "passive"))
      (node (ref "C41") (pin "2") (pinfunction "2_2") (pintype "passive"))
      (node (ref "C44") (pin "2") (pinfunction "2_2") (pintype "passive"))
      (node (ref "C45") (pin "2") (pinfunction "2_2") (pintype "passive"))
      (node (ref "C47") (pin "2") (pinfunction "2_2") (pintype "passive"))
      (node (ref "D7") (pin "1") (pinfunction "K_1") (pintype "passive"))
      (node (ref "Q2") (pin "2") (pinfunction "D_2") (pintype "passive"))
      (node (ref "R10") (pin "1") (pinfunction "1_1") (pintype "passive"))
      (node (ref "RA1_P") (pin "1") (pinfunction "1_1") (pintype "passive"))
    )
    (net (code "73") (name "unconnected-(J_IN-PadM)") (class "Default")
      (node (ref "J_IN") (pin "M") (pinfunction "M_M") (pintype "passive"))
    )
    (net (code "74") (name "unconnected-(J_OUT-PadM)") (class "Default")
      (node (ref "J_OUT") (pin "M") (pinfunction "M_M") (pintype "passive"))
    )
    (net (code "75") (name "unconnected-(U-BG1-Pad14)") (class "Default")
      (node (ref "U") (pin "14") (pinfunction "BG1_14") (pintype "output"))
    )
    (net (code "76") (name "unconnected-(U-BG2-Pad16)") (class "Default")
      (node (ref "U") (pin "16") (pinfunction "BG2_16") (pintype "output"))
    )
    (net (code "77") (name "unconnected-(U-BOOST1-Pad23)") (class "Default")
      (node (ref "U") (pin "23") (pinfunction "BOOST1_23") (pintype "output"))
    )
    (net (code "78") (name "unconnected-(U-BOOST2-Pad17)") (class "Default")
      (node (ref "U") (pin "17") (pinfunction "BOOST2_17") (pintype "output"))
    )
    (net (code "79") (name "unconnected-(U-CLKOUT-Pad10)") (class "Default")
      (node (ref "U") (pin "10") (pinfunction "CLKOUT_10") (pintype "output"))
    )
    (net (code "80") (name "unconnected-(U-CSN-Pad2)") (class "Default")
      (node (ref "U") (pin "2") (pinfunction "CSN_2") (pintype "input"))
    )
    (net (code "81") (name "unconnected-(U-CSNIN-Pad32)") (class "Default")
      (node (ref "U") (pin "32") (pinfunction "CSNIN_32") (pintype "input"))
    )
    (net (code "82") (name "unconnected-(U-CSNOUT-Pad30)") (class "Default")
      (node (ref "U") (pin "30") (pinfunction "CSNOUT_30") (pintype "input"))
    )
    (net (code "83") (name "unconnected-(U-CSP-Pad3)") (class "Default")
      (node (ref "U") (pin "3") (pinfunction "CSP_3") (pintype "input"))
    )
    (net (code "84") (name "unconnected-(U-CSPIN-Pad33)") (class "Default")
      (node (ref "U") (pin "33") (pinfunction "CSPIN_33") (pintype "input"))
    )
    (net (code "85") (name "unconnected-(U-CSPOUT-Pad31)") (class "Default")
      (node (ref "U") (pin "31") (pinfunction "CSPOUT_31") (pintype "input"))
    )
    (net (code "86") (name "unconnected-(U-EXP-Pad39)") (class "Default")
      (node (ref "U") (pin "39") (pinfunction "EXP_39") (pintype "power_in"))
    )
    (net (code "87") (name "unconnected-(U-EXTVCC-Pad29)") (class "Default")
      (node (ref "U") (pin "29") (pinfunction "EXTVCC_29") (pintype "input"))
    )
    (net (code "88") (name "unconnected-(U-FBIN-Pad5)") (class "Default")
      (node (ref "U") (pin "5") (pinfunction "FBIN_5") (pintype "input"))
    )
    (net (code "89") (name "unconnected-(U-FBOUT-Pad6)") (class "Default")
      (node (ref "U") (pin "6") (pinfunction "FBOUT_6") (pintype "output"))
    )
    (net (code "90") (name "unconnected-(U-GATEVCC-Pad15)") (class "Default")
      (node (ref "U") (pin "15") (pinfunction "GATEVCC_15") (pintype "power_in"))
    )
    (net (code "91") (name "unconnected-(U-GND-Pad13)") (class "Default")
      (node (ref "U") (pin "13") (pinfunction "GND_13") (pintype "power_in"))
    )
    (net (code "92") (name "unconnected-(U-IMON_IN-Pad38)") (class "Default")
      (node (ref "U") (pin "38") (pinfunction "IMON_IN_38") (pintype "input"))
    )
    (net (code "93") (name "unconnected-(U-IMON_OUT-Pad7)") (class "Default")
      (node (ref "U") (pin "7") (pinfunction "IMON_OUT_7") (pintype "output"))
    )
    (net (code "94") (name "unconnected-(U-INTVCC-Pad35)") (class "Default")
      (node (ref "U") (pin "35") (pinfunction "INTVCC_35") (pintype "output"))
    )
    (net (code "95") (name "unconnected-(U-LDO33-Pad4)") (class "Default")
      (node (ref "U") (pin "4") (pinfunction "LDO33_4") (pintype "output"))
    )
    (net (code "96") (name "unconnected-(U-MODE-Pad37)") (class "Default")
      (node (ref "U") (pin "37") (pinfunction "MODE_37") (pintype "input"))
    )
    (net (code "97") (name "unconnected-(U-RT-Pad12)") (class "Default")
      (node (ref "U") (pin "12") (pinfunction "RT_12") (pintype "passive"))
    )
    (net (code "98") (name "unconnected-(U-SRVO_FBIN-Pad25)") (class "Default")
      (node (ref "U") (pin "25") (pinfunction "SRVO_FBIN_25") (pintype "output"))
    )
    (net (code "99") (name "unconnected-(U-SRVO_FBOUT-Pad28)") (class "Default")
      (node (ref "U") (pin "28") (pinfunction "SRVO_FBOUT_28") (pintype "output"))
    )
    (net (code "100") (name "unconnected-(U-SRVO_IIN-Pad26)") (class "Default")
      (node (ref "U") (pin "26") (pinfunction "SRVO_IIN_26") (pintype "output"))
    )
    (net (code "101") (name "unconnected-(U-SRVO_IOUT-Pad27)") (class "Default")
      (node (ref "U") (pin "27") (pinfunction "SRVO_IOUT_27") (pintype "output"))
    )
    (net (code "102") (name "unconnected-(U-SS-Pad9)") (class "Default")
      (node (ref "U") (pin "9") (pinfunction "SS_9") (pintype "passive"))
    )
    (net (code "103") (name "unconnected-(U-SW1-Pad21)") (class "Default")
      (node (ref "U") (pin "21") (pinfunction "SW1_21") (pintype "output"))
    )
    (net (code "104") (name "unconnected-(U-SW2-Pad19)") (class "Default")
      (node (ref "U") (pin "19") (pinfunction "SW2_19") (pintype "output"))
    )
    (net (code "105") (name "unconnected-(U-SWEN-Pad36)") (class "Default")
      (node (ref "U") (pin "36") (pinfunction "SWEN_36") (pintype "input"))
    )
    (net (code "106") (name "unconnected-(U-SYNC-Pad11)") (class "Default")
      (node (ref "U") (pin "11") (pinfunction "SYNC_11") (pintype "input"))
    )
    (net (code "107") (name "unconnected-(U-TG1-Pad22)") (class "Default")
      (node (ref "U") (pin "22") (pinfunction "TG1_22") (pintype "output"))
    )
    (net (code "108") (name "unconnected-(U-TG2-Pad18)") (class "Default")
      (node (ref "U") (pin "18") (pinfunction "TG2_18") (pintype "output"))
    )
    (net (code "109") (name "unconnected-(U-VC-Pad8)") (class "Default")
      (node (ref "U") (pin "8") (pinfunction "VC_8") (pintype "output"))
    )
    (net (code "110") (name "unconnected-(U-VIN-Pad34)") (class "Default")
      (node (ref "U") (pin "34") (pinfunction "VIN_34") (pintype "input"))
    )
    (net (code "111") (name "unconnected-(U-~{SHDN}-Pad1)") (class "Default")
      (node (ref "U") (pin "1") (pinfunction "~{SHDN}_1") (pintype "input"))
    )
  )
)
